# uNimbus_board_2_v1_2.net
KiCad netlist of a schematic drawn in EAGLE
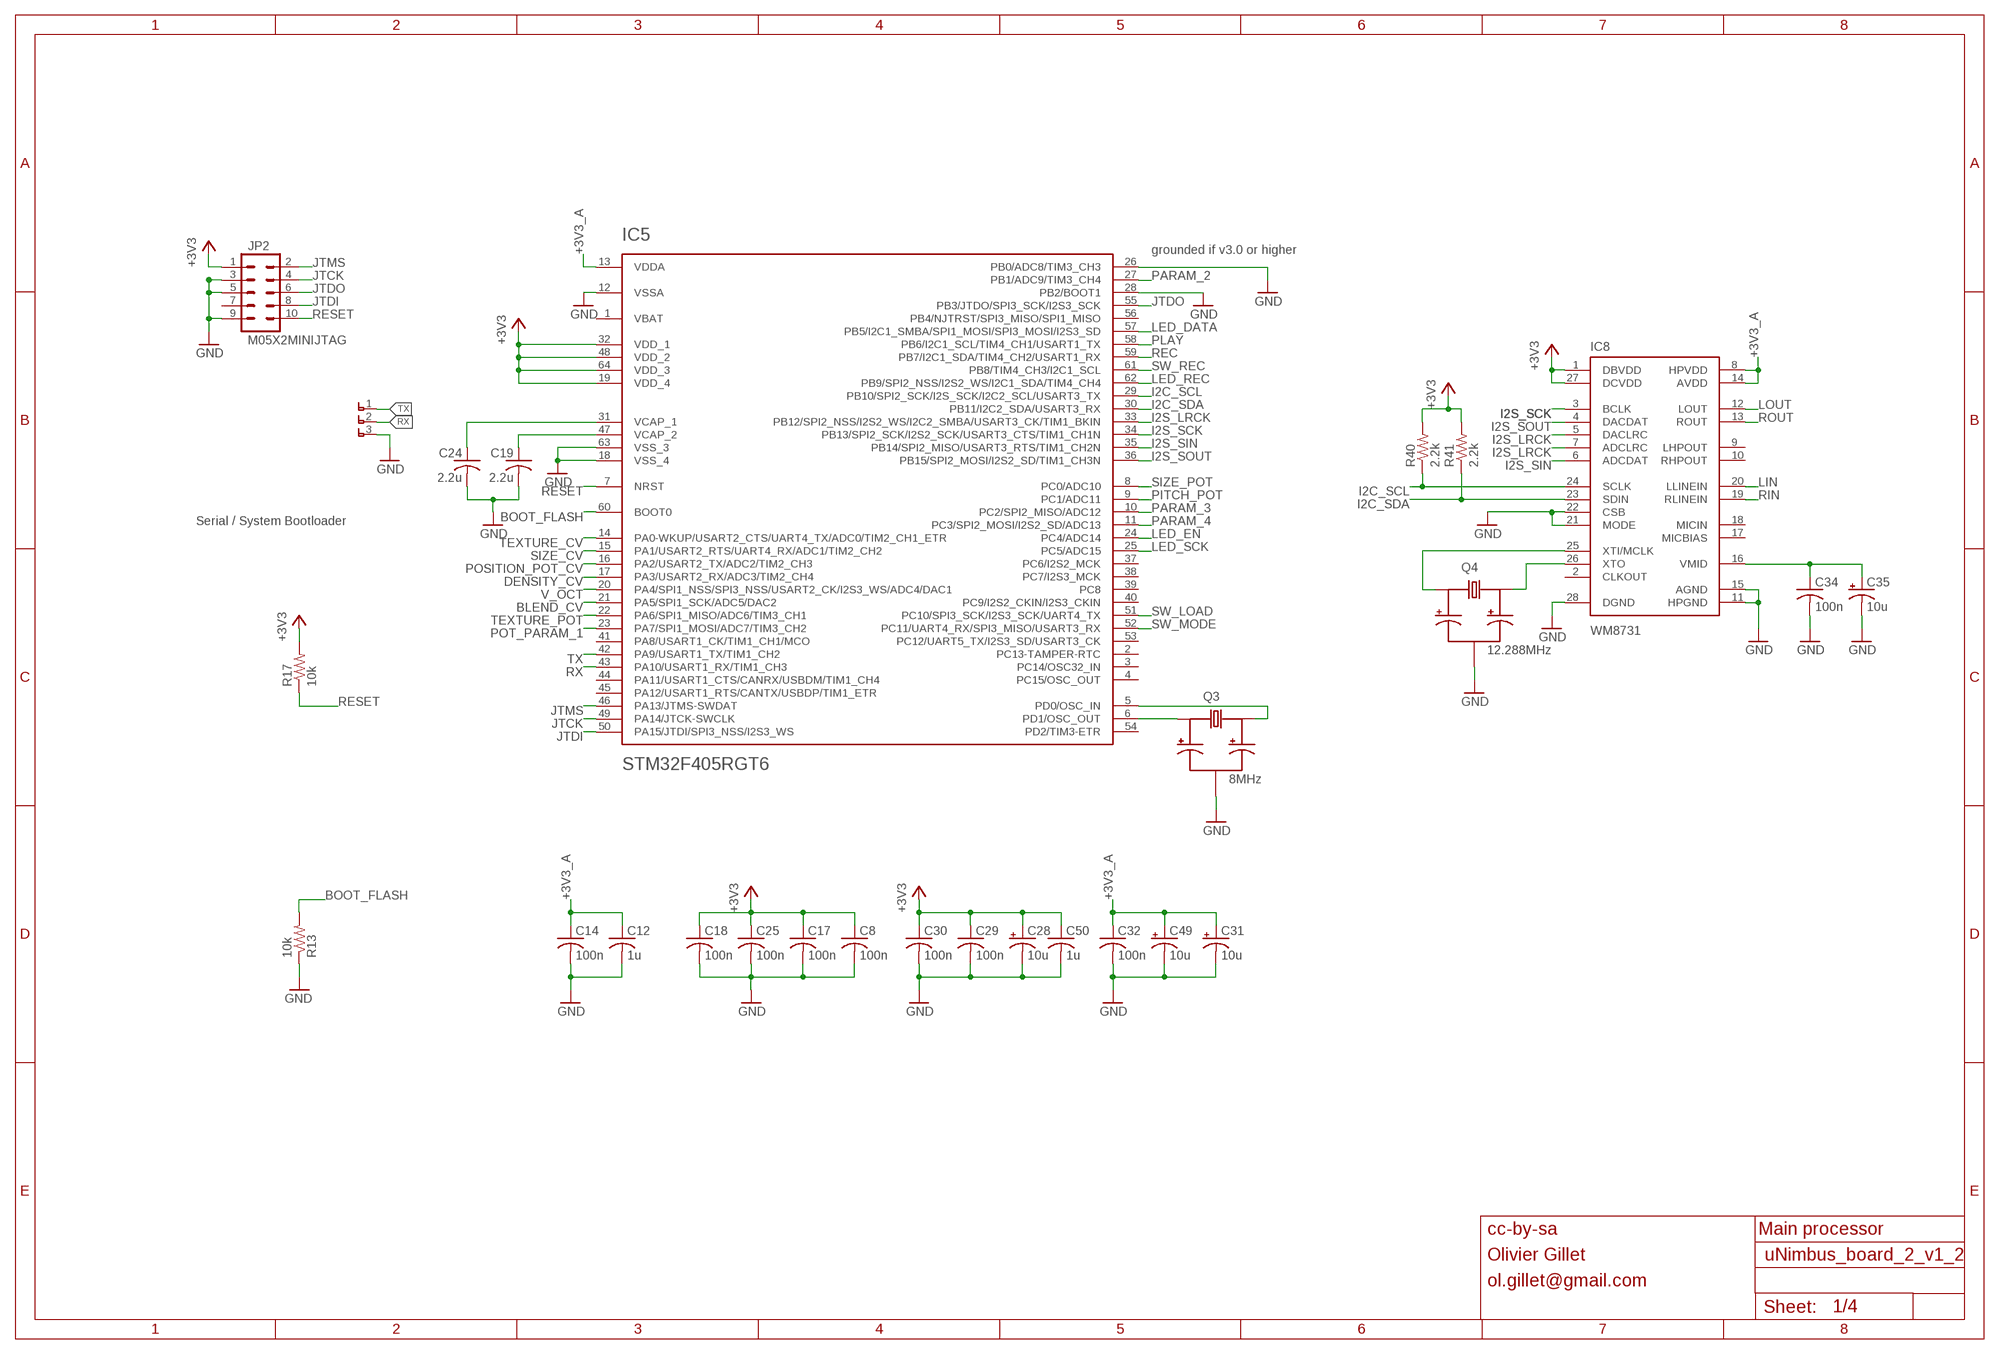
[diagram p0: schematic, sheet 1]
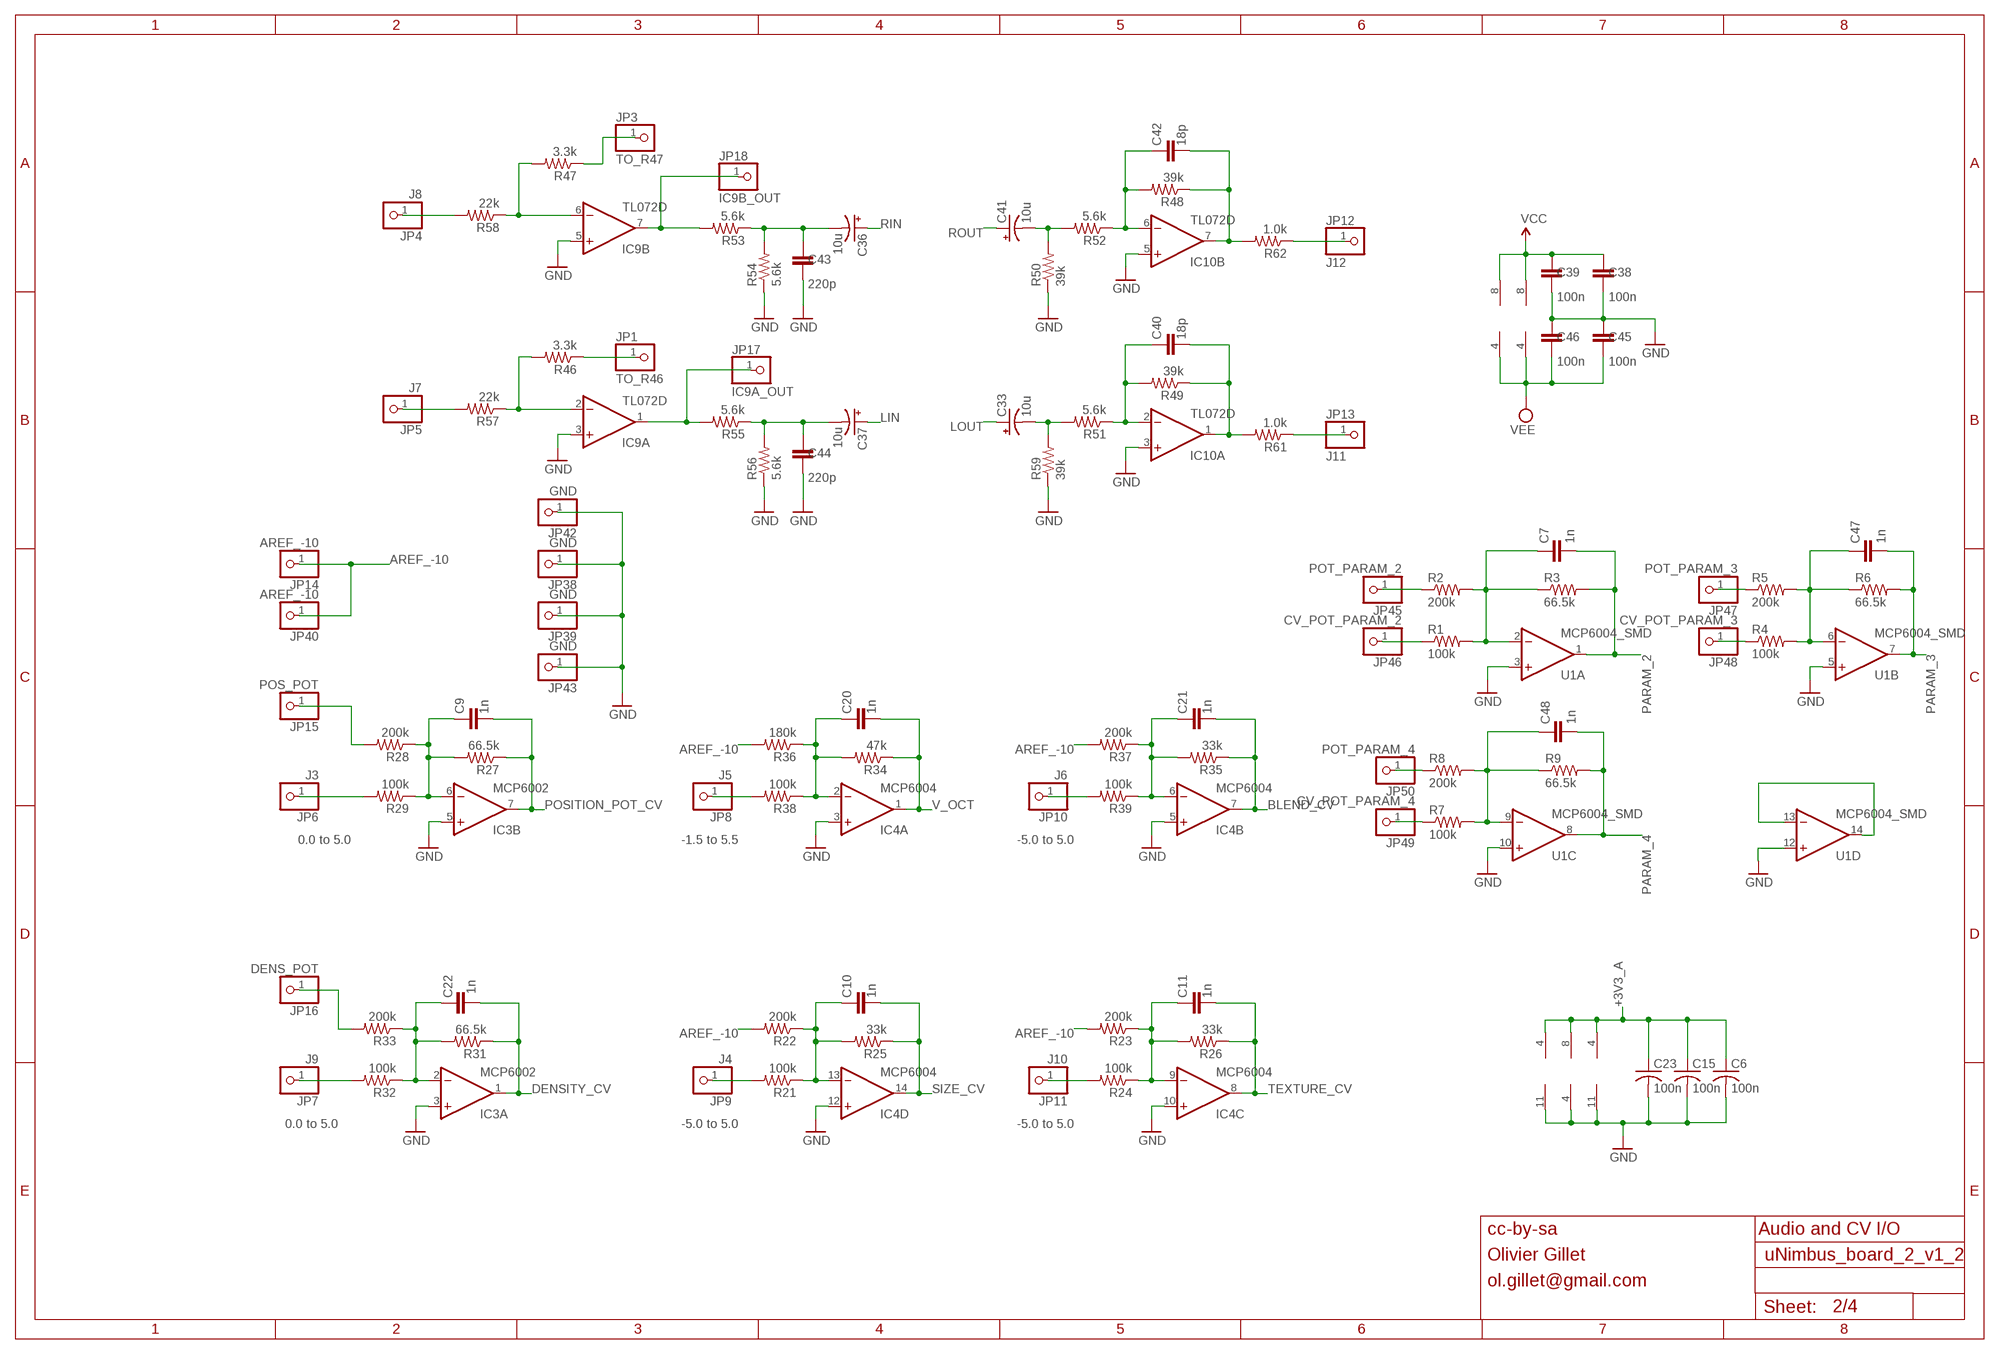
[diagram p1: schematic, sheet 2]
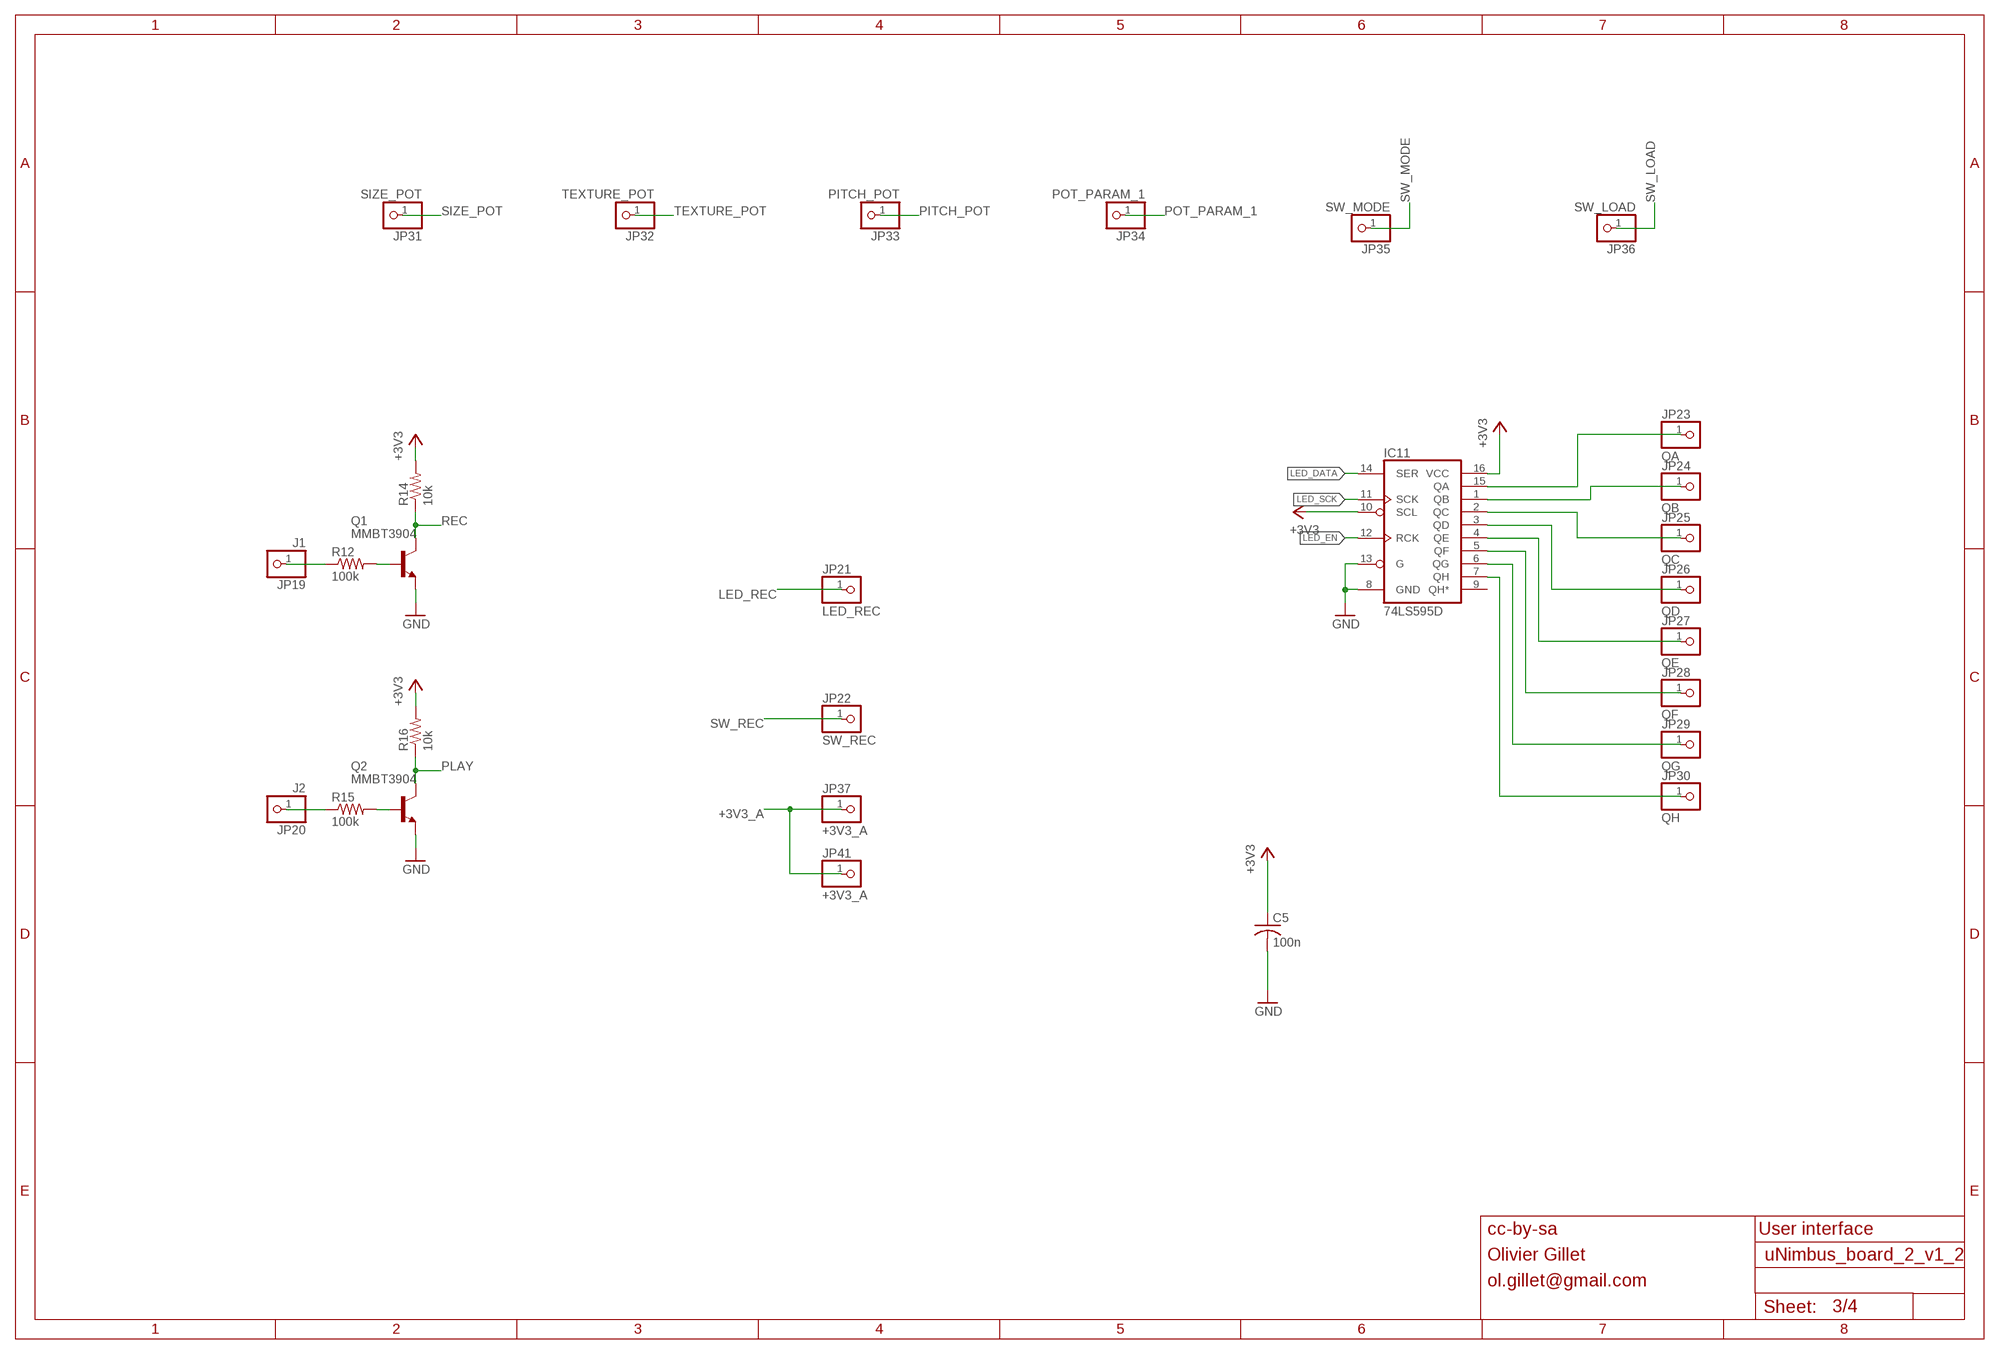
[diagram p2: schematic, sheet 3]
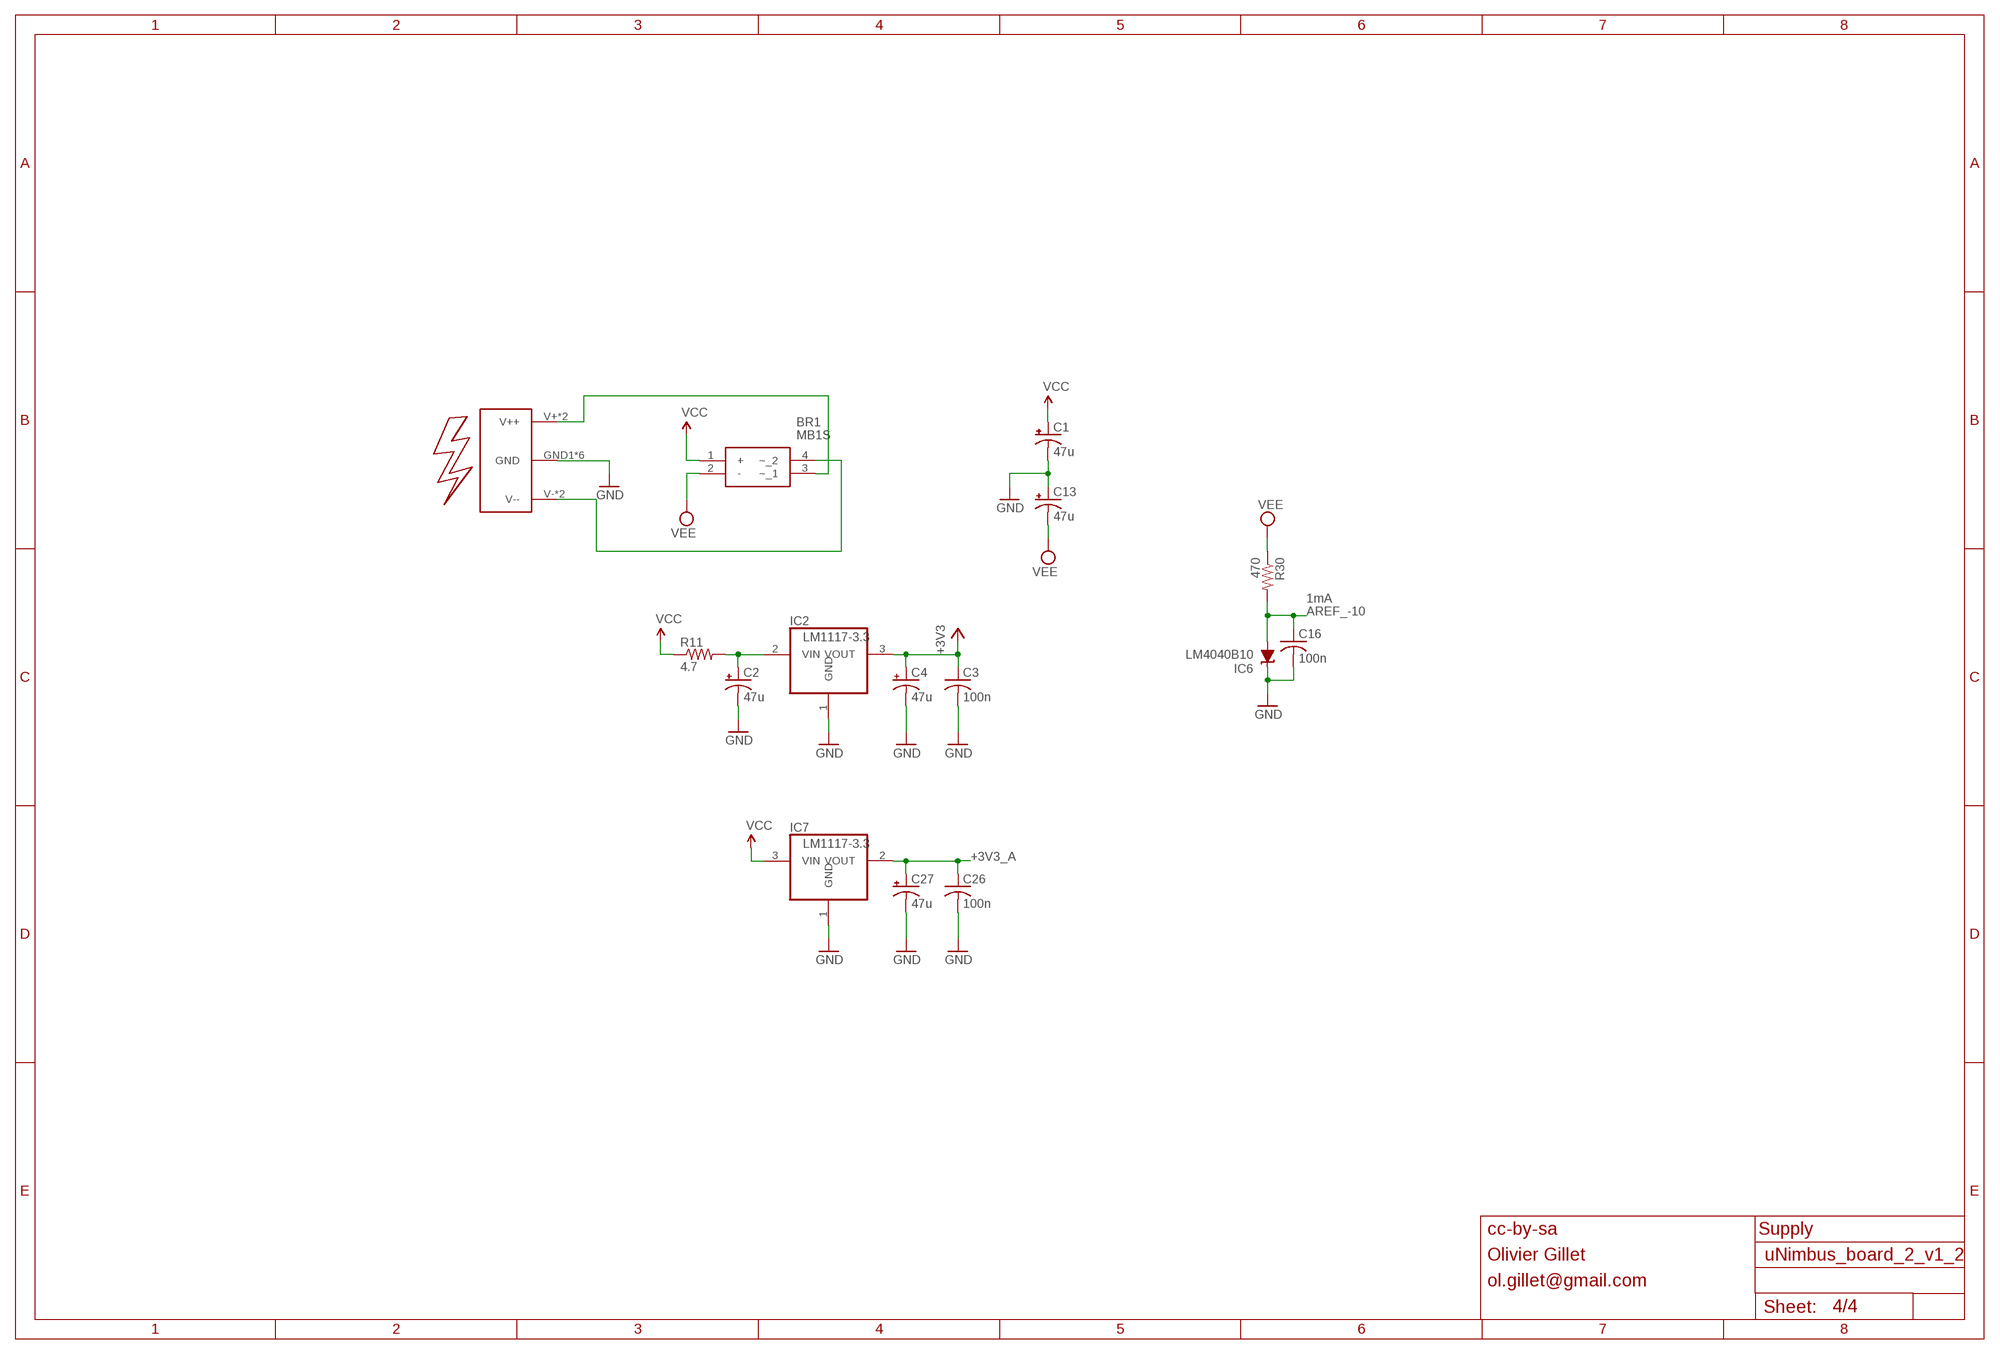
[diagram p3: schematic, sheet 4]

(export (version "E")
  (design (tool "Eeschema 10.0.6"))
  (components
    (comp (ref "C6")
      (value "100n")
      (footprint "eagle-import:C0603K")
      (libsource (lib "eagle-import") (part "rcl@1_C-USC0603K"))
    )
    (comp (ref "C7")
      (value "1n")
      (footprint "eagle-import:PARTS_AMAN_RESISTOR_0603")
      (libsource (lib "eagle-import") (part "PARTS_AMAN_CAPACITOR"))
    )
    (comp (ref "C9")
      (value "1n")
      (footprint "eagle-import:PARTS_AMAN_RESISTOR_0603")
      (libsource (lib "eagle-import") (part "PARTS_AMAN_CAPACITOR"))
    )
    (comp (ref "C10")
      (value "1n")
      (footprint "eagle-import:PARTS_AMAN_RESISTOR_0603")
      (libsource (lib "eagle-import") (part "PARTS_AMAN_CAPACITOR"))
    )
    (comp (ref "C11")
      (value "1n")
      (footprint "eagle-import:PARTS_AMAN_RESISTOR_0603")
      (libsource (lib "eagle-import") (part "PARTS_AMAN_CAPACITOR"))
    )
    (comp (ref "C15")
      (value "100n")
      (footprint "eagle-import:C0603K")
      (libsource (lib "eagle-import") (part "rcl@1_C-USC0603K"))
    )
    (comp (ref "C20")
      (value "1n")
      (footprint "eagle-import:PARTS_AMAN_RESISTOR_0603")
      (libsource (lib "eagle-import") (part "PARTS_AMAN_CAPACITOR"))
    )
    (comp (ref "C21")
      (value "1n")
      (footprint "eagle-import:PARTS_AMAN_RESISTOR_0603")
      (libsource (lib "eagle-import") (part "PARTS_AMAN_CAPACITOR"))
    )
    (comp (ref "C22")
      (value "1n")
      (footprint "eagle-import:PARTS_AMAN_RESISTOR_0603")
      (libsource (lib "eagle-import") (part "PARTS_AMAN_CAPACITOR"))
    )
    (comp (ref "C23")
      (value "100n")
      (footprint "eagle-import:C0603")
      (libsource (lib "eagle-import") (part "C-USC0603"))
    )
    (comp (ref "C33")
      (value "10u")
      (footprint "eagle-import:PANASONIC_B")
      (libsource (lib "eagle-import") (part "CPOL-USB"))
    )
    (comp (ref "C36")
      (value "10u")
      (footprint "eagle-import:PANASONIC_B")
      (libsource (lib "eagle-import") (part "CPOL-USB"))
    )
    (comp (ref "C37")
      (value "10u")
      (footprint "eagle-import:PANASONIC_B")
      (libsource (lib "eagle-import") (part "CPOL-USB"))
    )
    (comp (ref "C38")
      (value "100n")
      (footprint "eagle-import:PARTS_AMAN_RESISTOR_0603")
      (libsource (lib "eagle-import") (part "PARTS_AMAN_CAPACITOR"))
    )
    (comp (ref "C39")
      (value "100n")
      (footprint "eagle-import:PARTS_AMAN_RESISTOR_0603")
      (libsource (lib "eagle-import") (part "PARTS_AMAN_CAPACITOR"))
    )
    (comp (ref "C40")
      (value "18p")
      (footprint "eagle-import:PARTS_AMAN_RESISTOR_0603")
      (libsource (lib "eagle-import") (part "PARTS_AMAN_CAPACITOR"))
    )
    (comp (ref "C41")
      (value "10u")
      (footprint "eagle-import:PANASONIC_B")
      (libsource (lib "eagle-import") (part "CPOL-USB"))
    )
    (comp (ref "C42")
      (value "18p")
      (footprint "eagle-import:PARTS_AMAN_RESISTOR_0603")
      (libsource (lib "eagle-import") (part "PARTS_AMAN_CAPACITOR"))
    )
    (comp (ref "C43")
      (value "220p")
      (footprint "eagle-import:PARTS_AMAN_RESISTOR_0603")
      (libsource (lib "eagle-import") (part "PARTS_AMAN_CAPACITOR"))
    )
    (comp (ref "C44")
      (value "220p")
      (footprint "eagle-import:PARTS_AMAN_RESISTOR_0603")
      (libsource (lib "eagle-import") (part "PARTS_AMAN_CAPACITOR"))
    )
    (comp (ref "C45")
      (value "100n")
      (footprint "eagle-import:PARTS_AMAN_RESISTOR_0603")
      (libsource (lib "eagle-import") (part "PARTS_AMAN_CAPACITOR"))
    )
    (comp (ref "C46")
      (value "100n")
      (footprint "eagle-import:PARTS_AMAN_RESISTOR_0603")
      (libsource (lib "eagle-import") (part "PARTS_AMAN_CAPACITOR"))
    )
    (comp (ref "C47")
      (value "1n")
      (footprint "eagle-import:PARTS_AMAN_RESISTOR_0603")
      (libsource (lib "eagle-import") (part "PARTS_AMAN_CAPACITOR"))
    )
    (comp (ref "C48")
      (value "1n")
      (footprint "eagle-import:PARTS_AMAN_RESISTOR_0603")
      (libsource (lib "eagle-import") (part "PARTS_AMAN_CAPACITOR"))
    )
    (comp (ref "IC3")
      (value "MCP6002")
      (footprint "eagle-import:SO08")
      (libsource (lib "eagle-import") (part "TL072D"))
    )
    (comp (ref "IC4")
      (value "MCP6004")
      (footprint "eagle-import:SO14")
      (libsource (lib "eagle-import") (part "TL074D"))
    )
    (comp (ref "IC9")
      (value "TL072D")
      (footprint "eagle-import:SO08")
      (libsource (lib "eagle-import") (part "og-linear_TL072D"))
    )
    (comp (ref "IC10")
      (value "TL072D")
      (footprint "eagle-import:SO08")
      (libsource (lib "eagle-import") (part "og-linear_TL072D"))
    )
    (comp (ref "JP1")
      (value "TO_R46")
      (footprint "eagle-import:PARTS_AMAN_1X01")
      (libsource (lib "eagle-import") (part "PARTS_AMAN_PINHD-1X1"))
    )
    (comp (ref "JP3")
      (value "TO_R47")
      (footprint "eagle-import:PARTS_AMAN_1X01")
      (libsource (lib "eagle-import") (part "PARTS_AMAN_PINHD-1X1"))
    )
    (comp (ref "JP4")
      (value "J8")
      (footprint "eagle-import:PARTS_AMAN_1X01")
      (libsource (lib "eagle-import") (part "PARTS_AMAN_PINHD-1X1"))
    )
    (comp (ref "JP5")
      (value "J7")
      (footprint "eagle-import:PARTS_AMAN_1X01")
      (libsource (lib "eagle-import") (part "PARTS_AMAN_PINHD-1X1"))
    )
    (comp (ref "JP6")
      (value "J3")
      (footprint "eagle-import:PARTS_AMAN_1X01")
      (libsource (lib "eagle-import") (part "PARTS_AMAN_PINHD-1X1"))
    )
    (comp (ref "JP7")
      (value "J9")
      (footprint "eagle-import:PARTS_AMAN_1X01")
      (libsource (lib "eagle-import") (part "PARTS_AMAN_PINHD-1X1"))
    )
    (comp (ref "JP8")
      (value "J5")
      (footprint "eagle-import:PARTS_AMAN_1X01")
      (libsource (lib "eagle-import") (part "PARTS_AMAN_PINHD-1X1"))
    )
    (comp (ref "JP9")
      (value "J4")
      (footprint "eagle-import:PARTS_AMAN_1X01")
      (libsource (lib "eagle-import") (part "PARTS_AMAN_PINHD-1X1"))
    )
    (comp (ref "JP10")
      (value "J6")
      (footprint "eagle-import:PARTS_AMAN_1X01")
      (libsource (lib "eagle-import") (part "PARTS_AMAN_PINHD-1X1"))
    )
    (comp (ref "JP11")
      (value "J10")
      (footprint "eagle-import:PARTS_AMAN_1X01")
      (libsource (lib "eagle-import") (part "PARTS_AMAN_PINHD-1X1"))
    )
    (comp (ref "JP12")
      (value "J12")
      (footprint "eagle-import:PARTS_AMAN_1X01")
      (libsource (lib "eagle-import") (part "PARTS_AMAN_PINHD-1X1"))
    )
    (comp (ref "JP13")
      (value "J11")
      (footprint "eagle-import:PARTS_AMAN_1X01")
      (libsource (lib "eagle-import") (part "PARTS_AMAN_PINHD-1X1"))
    )
    (comp (ref "JP14")
      (value "AREF_-10")
      (footprint "eagle-import:PARTS_AMAN_1X01")
      (libsource (lib "eagle-import") (part "PARTS_AMAN_PINHD-1X1"))
    )
    (comp (ref "JP15")
      (value "POS_POT")
      (footprint "eagle-import:PARTS_AMAN_1X01")
      (libsource (lib "eagle-import") (part "PARTS_AMAN_PINHD-1X1"))
    )
    (comp (ref "JP16")
      (value "DENS_POT")
      (footprint "eagle-import:PARTS_AMAN_1X01")
      (libsource (lib "eagle-import") (part "PARTS_AMAN_PINHD-1X1"))
    )
    (comp (ref "JP17")
      (value "IC9A_OUT")
      (footprint "eagle-import:PARTS_AMAN_1X01")
      (libsource (lib "eagle-import") (part "PARTS_AMAN_PINHD-1X1"))
    )
    (comp (ref "JP18")
      (value "IC9B_OUT")
      (footprint "eagle-import:PARTS_AMAN_1X01")
      (libsource (lib "eagle-import") (part "PARTS_AMAN_PINHD-1X1"))
    )
    (comp (ref "JP38")
      (value "GND")
      (footprint "eagle-import:PARTS_AMAN_1X01")
      (libsource (lib "eagle-import") (part "PARTS_AMAN_PINHD-1X1"))
    )
    (comp (ref "JP39")
      (value "GND")
      (footprint "eagle-import:PARTS_AMAN_1X01")
      (libsource (lib "eagle-import") (part "PARTS_AMAN_PINHD-1X1"))
    )
    (comp (ref "JP40")
      (value "AREF_-10")
      (footprint "eagle-import:PARTS_AMAN_1X01")
      (libsource (lib "eagle-import") (part "PARTS_AMAN_PINHD-1X1"))
    )
    (comp (ref "JP42")
      (value "GND")
      (footprint "eagle-import:PARTS_AMAN_1X01")
      (libsource (lib "eagle-import") (part "PARTS_AMAN_PINHD-1X1"))
    )
    (comp (ref "JP43")
      (value "GND")
      (footprint "eagle-import:PARTS_AMAN_1X01")
      (libsource (lib "eagle-import") (part "PARTS_AMAN_PINHD-1X1"))
    )
    (comp (ref "JP45")
      (value "POT_PARAM_2")
      (footprint "eagle-import:PARTS_AMAN_1X01")
      (libsource (lib "eagle-import") (part "PARTS_AMAN_PINHD-1X1"))
    )
    (comp (ref "JP46")
      (value "CV_POT_PARAM_2")
      (footprint "eagle-import:PARTS_AMAN_1X01")
      (libsource (lib "eagle-import") (part "PARTS_AMAN_PINHD-1X1"))
    )
    (comp (ref "JP47")
      (value "POT_PARAM_3")
      (footprint "eagle-import:PARTS_AMAN_1X01")
      (libsource (lib "eagle-import") (part "PARTS_AMAN_PINHD-1X1"))
    )
    (comp (ref "JP48")
      (value "CV_POT_PARAM_3")
      (footprint "eagle-import:PARTS_AMAN_1X01")
      (libsource (lib "eagle-import") (part "PARTS_AMAN_PINHD-1X1"))
    )
    (comp (ref "JP49")
      (value "CV_POT_PARAM_4")
      (footprint "eagle-import:PARTS_AMAN_1X01")
      (libsource (lib "eagle-import") (part "PARTS_AMAN_PINHD-1X1"))
    )
    (comp (ref "JP50")
      (value "POT_PARAM_4")
      (footprint "eagle-import:PARTS_AMAN_1X01")
      (libsource (lib "eagle-import") (part "PARTS_AMAN_PINHD-1X1"))
    )
    (comp (ref "R1")
      (value "100k")
      (footprint "eagle-import:PARTS_AMAN_RESISTOR_0603")
      (libsource (lib "eagle-import") (part "PARTS_AMAN_RESISTOR"))
    )
    (comp (ref "R2")
      (value "200k")
      (footprint "eagle-import:PARTS_AMAN_RESISTOR_0603")
      (libsource (lib "eagle-import") (part "PARTS_AMAN_RESISTOR"))
    )
    (comp (ref "R3")
      (value "66.5k")
      (footprint "eagle-import:PARTS_AMAN_RESISTOR_0603")
      (libsource (lib "eagle-import") (part "PARTS_AMAN_RESISTOR"))
    )
    (comp (ref "R4")
      (value "100k")
      (footprint "eagle-import:PARTS_AMAN_RESISTOR_0603")
      (libsource (lib "eagle-import") (part "PARTS_AMAN_RESISTOR"))
    )
    (comp (ref "R5")
      (value "200k")
      (footprint "eagle-import:PARTS_AMAN_RESISTOR_0603")
      (libsource (lib "eagle-import") (part "PARTS_AMAN_RESISTOR"))
    )
    (comp (ref "R6")
      (value "66.5k")
      (footprint "eagle-import:PARTS_AMAN_RESISTOR_0603")
      (libsource (lib "eagle-import") (part "PARTS_AMAN_RESISTOR"))
    )
    (comp (ref "R7")
      (value "100k")
      (footprint "eagle-import:PARTS_AMAN_RESISTOR_0603")
      (libsource (lib "eagle-import") (part "PARTS_AMAN_RESISTOR"))
    )
    (comp (ref "R8")
      (value "200k")
      (footprint "eagle-import:PARTS_AMAN_RESISTOR_0603")
      (libsource (lib "eagle-import") (part "PARTS_AMAN_RESISTOR"))
    )
    (comp (ref "R9")
      (value "66.5k")
      (footprint "eagle-import:PARTS_AMAN_RESISTOR_0603")
      (libsource (lib "eagle-import") (part "PARTS_AMAN_RESISTOR"))
    )
    (comp (ref "R21")
      (value "100k")
      (footprint "eagle-import:PARTS_AMAN_RESISTOR_0603")
      (libsource (lib "eagle-import") (part "PARTS_AMAN_RESISTOR"))
    )
    (comp (ref "R22")
      (value "200k")
      (footprint "eagle-import:PARTS_AMAN_RESISTOR_0603")
      (libsource (lib "eagle-import") (part "PARTS_AMAN_RESISTOR"))
    )
    (comp (ref "R23")
      (value "200k")
      (footprint "eagle-import:PARTS_AMAN_RESISTOR_0603")
      (libsource (lib "eagle-import") (part "PARTS_AMAN_RESISTOR"))
    )
    (comp (ref "R24")
      (value "100k")
      (footprint "eagle-import:PARTS_AMAN_RESISTOR_0603")
      (libsource (lib "eagle-import") (part "PARTS_AMAN_RESISTOR"))
    )
    (comp (ref "R25")
      (value "33k")
      (footprint "eagle-import:PARTS_AMAN_RESISTOR_0603")
      (libsource (lib "eagle-import") (part "PARTS_AMAN_RESISTOR"))
    )
    (comp (ref "R26")
      (value "33k")
      (footprint "eagle-import:PARTS_AMAN_RESISTOR_0603")
      (libsource (lib "eagle-import") (part "PARTS_AMAN_RESISTOR"))
    )
    (comp (ref "R27")
      (value "66.5k")
      (footprint "eagle-import:PARTS_AMAN_RESISTOR_0603")
      (libsource (lib "eagle-import") (part "PARTS_AMAN_RESISTOR"))
    )
    (comp (ref "R28")
      (value "200k")
      (footprint "eagle-import:PARTS_AMAN_RESISTOR_0603")
      (libsource (lib "eagle-import") (part "PARTS_AMAN_RESISTOR"))
    )
    (comp (ref "R29")
      (value "100k")
      (footprint "eagle-import:PARTS_AMAN_RESISTOR_0603")
      (libsource (lib "eagle-import") (part "PARTS_AMAN_RESISTOR"))
    )
    (comp (ref "R31")
      (value "66.5k")
      (footprint "eagle-import:PARTS_AMAN_RESISTOR_0603")
      (libsource (lib "eagle-import") (part "PARTS_AMAN_RESISTOR"))
    )
    (comp (ref "R32")
      (value "100k")
      (footprint "eagle-import:PARTS_AMAN_RESISTOR_0603")
      (libsource (lib "eagle-import") (part "PARTS_AMAN_RESISTOR"))
    )
    (comp (ref "R33")
      (value "200k")
      (footprint "eagle-import:PARTS_AMAN_RESISTOR_0603")
      (libsource (lib "eagle-import") (part "PARTS_AMAN_RESISTOR"))
    )
    (comp (ref "R34")
      (value "47k")
      (footprint "eagle-import:PARTS_AMAN_RESISTOR_0603")
      (libsource (lib "eagle-import") (part "PARTS_AMAN_RESISTOR"))
    )
    (comp (ref "R35")
      (value "33k")
      (footprint "eagle-import:PARTS_AMAN_RESISTOR_0603")
      (libsource (lib "eagle-import") (part "PARTS_AMAN_RESISTOR"))
    )
    (comp (ref "R36")
      (value "180k")
      (footprint "eagle-import:PARTS_AMAN_RESISTOR_0603")
      (libsource (lib "eagle-import") (part "PARTS_AMAN_RESISTOR"))
    )
    (comp (ref "R37")
      (value "200k")
      (footprint "eagle-import:PARTS_AMAN_RESISTOR_0603")
      (libsource (lib "eagle-import") (part "PARTS_AMAN_RESISTOR"))
    )
    (comp (ref "R38")
      (value "100k")
      (footprint "eagle-import:PARTS_AMAN_RESISTOR_0603")
      (libsource (lib "eagle-import") (part "PARTS_AMAN_RESISTOR"))
    )
    (comp (ref "R39")
      (value "100k")
      (footprint "eagle-import:PARTS_AMAN_RESISTOR_0603")
      (libsource (lib "eagle-import") (part "PARTS_AMAN_RESISTOR"))
    )
    (comp (ref "R46")
      (value "3.3k")
      (footprint "eagle-import:PARTS_AMAN_RESISTOR_0603")
      (libsource (lib "eagle-import") (part "PARTS_AMAN_RESISTOR"))
    )
    (comp (ref "R47")
      (value "3.3k")
      (footprint "eagle-import:PARTS_AMAN_RESISTOR_0603")
      (libsource (lib "eagle-import") (part "PARTS_AMAN_RESISTOR"))
    )
    (comp (ref "R48")
      (value "39k")
      (footprint "eagle-import:PARTS_AMAN_RESISTOR_0603")
      (libsource (lib "eagle-import") (part "PARTS_AMAN_RESISTOR"))
    )
    (comp (ref "R49")
      (value "39k")
      (footprint "eagle-import:PARTS_AMAN_RESISTOR_0603")
      (libsource (lib "eagle-import") (part "PARTS_AMAN_RESISTOR"))
    )
    (comp (ref "R50")
      (value "39k")
      (footprint "eagle-import:PARTS_AMAN_RESISTOR_0603")
      (libsource (lib "eagle-import") (part "PARTS_AMAN_RESISTOR"))
    )
    (comp (ref "R51")
      (value "5.6k")
      (footprint "eagle-import:PARTS_AMAN_RESISTOR_0603")
      (libsource (lib "eagle-import") (part "PARTS_AMAN_RESISTOR"))
    )
    (comp (ref "R52")
      (value "5.6k")
      (footprint "eagle-import:PARTS_AMAN_RESISTOR_0603")
      (libsource (lib "eagle-import") (part "PARTS_AMAN_RESISTOR"))
    )
    (comp (ref "R53")
      (value "5.6k")
      (footprint "eagle-import:PARTS_AMAN_RESISTOR_0603")
      (libsource (lib "eagle-import") (part "PARTS_AMAN_RESISTOR"))
    )
    (comp (ref "R54")
      (value "5.6k")
      (footprint "eagle-import:PARTS_AMAN_RESISTOR_0603")
      (libsource (lib "eagle-import") (part "PARTS_AMAN_RESISTOR"))
    )
    (comp (ref "R55")
      (value "5.6k")
      (footprint "eagle-import:PARTS_AMAN_RESISTOR_0603")
      (libsource (lib "eagle-import") (part "PARTS_AMAN_RESISTOR"))
    )
    (comp (ref "R56")
      (value "5.6k")
      (footprint "eagle-import:PARTS_AMAN_RESISTOR_0603")
      (libsource (lib "eagle-import") (part "PARTS_AMAN_RESISTOR"))
    )
    (comp (ref "R57")
      (value "22k")
      (footprint "eagle-import:PARTS_AMAN_RESISTOR_0603")
      (libsource (lib "eagle-import") (part "PARTS_AMAN_RESISTOR"))
    )
    (comp (ref "R58")
      (value "22k")
      (footprint "eagle-import:PARTS_AMAN_RESISTOR_0603")
      (libsource (lib "eagle-import") (part "PARTS_AMAN_RESISTOR"))
    )
    (comp (ref "R59")
      (value "39k")
      (footprint "eagle-import:PARTS_AMAN_RESISTOR_0603")
      (libsource (lib "eagle-import") (part "PARTS_AMAN_RESISTOR"))
    )
    (comp (ref "R61")
      (value "1.0k")
      (footprint "eagle-import:PARTS_AMAN_RESISTOR_0603")
      (libsource (lib "eagle-import") (part "PARTS_AMAN_RESISTOR"))
    )
    (comp (ref "R62")
      (value "1.0k")
      (footprint "eagle-import:PARTS_AMAN_RESISTOR_0603")
      (libsource (lib "eagle-import") (part "PARTS_AMAN_RESISTOR"))
    )
    (comp (ref "U1")
      (value "MCP6004_SMD")
      (footprint "eagle-import:SO14")
      (libsource (lib "eagle-import") (part "MCP6004_SMD"))
    )
    (comp (ref "C5")
      (value "100n")
      (footprint "eagle-import:C0603")
      (libsource (lib "eagle-import") (part "C-USC0603"))
    )
    (comp (ref "IC11")
      (value "74LS595D")
      (footprint "eagle-import:SO16")
      (libsource (lib "eagle-import") (part "74595DLS"))
    )
    (comp (ref "JP19")
      (value "J1")
      (footprint "eagle-import:PARTS_AMAN_1X01")
      (libsource (lib "eagle-import") (part "PARTS_AMAN_PINHD-1X1"))
    )
    (comp (ref "JP20")
      (value "J2")
      (footprint "eagle-import:PARTS_AMAN_1X01")
      (libsource (lib "eagle-import") (part "PARTS_AMAN_PINHD-1X1"))
    )
    (comp (ref "JP21")
      (value "LED_REC")
      (footprint "eagle-import:PARTS_AMAN_1X01")
      (libsource (lib "eagle-import") (part "PARTS_AMAN_PINHD-1X1"))
    )
    (comp (ref "JP22")
      (value "SW_REC")
      (footprint "eagle-import:PARTS_AMAN_1X01")
      (libsource (lib "eagle-import") (part "PARTS_AMAN_PINHD-1X1"))
    )
    (comp (ref "JP23")
      (value "QA")
      (footprint "eagle-import:PARTS_AMAN_1X01")
      (libsource (lib "eagle-import") (part "PARTS_AMAN_PINHD-1X1"))
    )
    (comp (ref "JP24")
      (value "QB")
      (footprint "eagle-import:PARTS_AMAN_1X01")
      (libsource (lib "eagle-import") (part "PARTS_AMAN_PINHD-1X1"))
    )
    (comp (ref "JP25")
      (value "QC")
      (footprint "eagle-import:PARTS_AMAN_1X01")
      (libsource (lib "eagle-import") (part "PARTS_AMAN_PINHD-1X1"))
    )
    (comp (ref "JP26")
      (value "QD")
      (footprint "eagle-import:PARTS_AMAN_1X01")
      (libsource (lib "eagle-import") (part "PARTS_AMAN_PINHD-1X1"))
    )
    (comp (ref "JP27")
      (value "QE")
      (footprint "eagle-import:PARTS_AMAN_1X01")
      (libsource (lib "eagle-import") (part "PARTS_AMAN_PINHD-1X1"))
    )
    (comp (ref "JP28")
      (value "QF")
      (footprint "eagle-import:PARTS_AMAN_1X01")
      (libsource (lib "eagle-import") (part "PARTS_AMAN_PINHD-1X1"))
    )
    (comp (ref "JP29")
      (value "QG")
      (footprint "eagle-import:PARTS_AMAN_1X01")
      (libsource (lib "eagle-import") (part "PARTS_AMAN_PINHD-1X1"))
    )
    (comp (ref "JP30")
      (value "QH")
      (footprint "eagle-import:PARTS_AMAN_1X01")
      (libsource (lib "eagle-import") (part "PARTS_AMAN_PINHD-1X1"))
    )
    (comp (ref "JP31")
      (value "SIZE_POT")
      (footprint "eagle-import:PARTS_AMAN_1X01")
      (libsource (lib "eagle-import") (part "PARTS_AMAN_PINHD-1X1"))
    )
    (comp (ref "JP32")
      (value "TEXTURE_POT")
      (footprint "eagle-import:PARTS_AMAN_1X01")
      (libsource (lib "eagle-import") (part "PARTS_AMAN_PINHD-1X1"))
    )
    (comp (ref "JP33")
      (value "PITCH_POT")
      (footprint "eagle-import:PARTS_AMAN_1X01")
      (libsource (lib "eagle-import") (part "PARTS_AMAN_PINHD-1X1"))
    )
    (comp (ref "JP34")
      (value "POT_PARAM_1")
      (footprint "eagle-import:PARTS_AMAN_1X01")
      (libsource (lib "eagle-import") (part "PARTS_AMAN_PINHD-1X1"))
    )
    (comp (ref "JP35")
      (value "SW_MODE")
      (footprint "eagle-import:PARTS_AMAN_1X01")
      (libsource (lib "eagle-import") (part "PARTS_AMAN_PINHD-1X1"))
    )
    (comp (ref "JP36")
      (value "SW_LOAD")
      (footprint "eagle-import:PARTS_AMAN_1X01")
      (libsource (lib "eagle-import") (part "PARTS_AMAN_PINHD-1X1"))
    )
    (comp (ref "JP37")
      (value "+3V3_A")
      (footprint "eagle-import:PARTS_AMAN_1X01")
      (libsource (lib "eagle-import") (part "PARTS_AMAN_PINHD-1X1"))
    )
    (comp (ref "JP41")
      (value "+3V3_A")
      (footprint "eagle-import:PARTS_AMAN_1X01")
      (libsource (lib "eagle-import") (part "PARTS_AMAN_PINHD-1X1"))
    )
    (comp (ref "Q1")
      (value "MMBT3904")
      (footprint "eagle-import:SOT23-BEC")
      (libsource (lib "eagle-import") (part "-NPN-SOT23-BECMMBT3904LT1"))
    )
    (comp (ref "Q2")
      (value "MMBT3904")
      (footprint "eagle-import:SOT23-BEC")
      (libsource (lib "eagle-import") (part "-NPN-SOT23-BECMMBT3904LT1"))
    )
    (comp (ref "R12")
      (value "100k")
      (footprint "eagle-import:R0603")
      (libsource (lib "eagle-import") (part "R-US_R0603"))
    )
    (comp (ref "R14")
      (value "10k")
      (footprint "eagle-import:R0603")
      (libsource (lib "eagle-import") (part "R-US_R0603"))
    )
    (comp (ref "R15")
      (value "100k")
      (footprint "eagle-import:R0603")
      (libsource (lib "eagle-import") (part "R-US_R0603"))
    )
    (comp (ref "R16")
      (value "10k")
      (footprint "eagle-import:R0603")
      (libsource (lib "eagle-import") (part "R-US_R0603"))
    )
    (comp (ref "BR1")
      (value "MB1S")
      (footprint "eagle-import:SOP245P670X290-4N")
      (fields (field (name "MOUSER_PART_NUMBER") "512-MB1S") (field (name "RS_PART_NUMBER") "7613650P"))
      (libsource (lib "eagle-import") (part "MB1S"))
    )
    (comp (ref "C1")
      (value "47u")
      (footprint "eagle-import:153CLV-0505")
      (libsource (lib "eagle-import") (part "CPOL-US153CLV-0505"))
    )
    (comp (ref "C2")
      (value "47u")
      (footprint "eagle-import:153CLV-0505")
      (libsource (lib "eagle-import") (part "rcl@1_CPOL-US153CLV-0505"))
    )
    (comp (ref "C3")
      (value "100n")
      (footprint "eagle-import:C0603")
      (libsource (lib "eagle-import") (part "C-USC0603"))
    )
    (comp (ref "C4")
      (value "47u")
      (footprint "eagle-import:153CLV-0505")
      (libsource (lib "eagle-import") (part "CPOL-US153CLV-0505"))
    )
    (comp (ref "C13")
      (value "47u")
      (footprint "eagle-import:153CLV-0505")
      (libsource (lib "eagle-import") (part "CPOL-US153CLV-0505"))
    )
    (comp (ref "C16")
      (value "100n")
      (footprint "eagle-import:C0603")
      (libsource (lib "eagle-import") (part "C-USC0603"))
    )
    (comp (ref "C26")
      (value "100n")
      (footprint "eagle-import:C0603")
      (libsource (lib "eagle-import") (part "C-USC0603"))
    )
    (comp (ref "C27")
      (value "47u")
      (footprint "eagle-import:153CLV-0505")
      (libsource (lib "eagle-import") (part "CPOL-US153CLV-0505"))
    )
    (comp (ref "IC2")
      (value "LM1117-3.3")
      (footprint "eagle-import:TO252")
      (libsource (lib "eagle-import") (part "REG1117T"))
    )
    (comp (ref "IC6")
      (value "LM4040B10")
      (footprint "eagle-import:DBZ_R-PDSO-G3")
      (libsource (lib "eagle-import") (part "LM4041DBZB12"))
    )
    (comp (ref "IC7")
      (value "LM1117-3.3")
      (footprint "eagle-import:SOT223")
      (libsource (lib "eagle-import") (part "REG1117"))
    )
    (comp (ref "R11")
      (value "4.7")
      (footprint "eagle-import:R1206")
      (libsource (lib "eagle-import") (part "R-US_R1206"))
    )
    (comp (ref "R30")
      (value "470")
      (footprint "eagle-import:R0603")
      (libsource (lib "eagle-import") (part "R-US_R0603"))
    )
    (comp (ref "U$2")
      (value "EURO_POWER2")
      (footprint "eagle-import:EURO_POWER2")
      (libsource (lib "eagle-import") (part "EURO_POWER2"))
    )
    (comp (ref "C8")
      (value "100n")
      (footprint "eagle-import:C0603")
      (libsource (lib "eagle-import") (part "C-USC0603"))
    )
    (comp (ref "C12")
      (value "1u")
      (footprint "eagle-import:C0603K")
      (libsource (lib "eagle-import") (part "C-USC0603K"))
    )
    (comp (ref "C14")
      (value "100n")
      (footprint "eagle-import:C0603K")
      (libsource (lib "eagle-import") (part "C-USC0603K"))
    )
    (comp (ref "C17")
      (value "100n")
      (footprint "eagle-import:C0603K")
      (libsource (lib "eagle-import") (part "C-USC0603K"))
    )
    (comp (ref "C18")
      (value "100n")
      (footprint "eagle-import:C0603K")
      (libsource (lib "eagle-import") (part "C-USC0603K"))
    )
    (comp (ref "C19")
      (value "2.2u")
      (footprint "eagle-import:C0805K")
      (libsource (lib "eagle-import") (part "rcl@1_C-USC0805K"))
    )
    (comp (ref "C24")
      (value "2.2u")
      (footprint "eagle-import:C0805K")
      (libsource (lib "eagle-import") (part "rcl@1_C-USC0805K"))
    )
    (comp (ref "C25")
      (value "100n")
      (footprint "eagle-import:C0603K")
      (libsource (lib "eagle-import") (part "rcl@1_C-USC0603K"))
    )
    (comp (ref "C28")
      (value "10u")
      (footprint "eagle-import:153CLV-0405")
      (libsource (lib "eagle-import") (part "rcl@1_CPOL-US153CLV-0405"))
    )
    (comp (ref "C29")
      (value "100n")
      (footprint "eagle-import:C0603K")
      (libsource (lib "eagle-import") (part "C-USC0603K"))
    )
    (comp (ref "C30")
      (value "100n")
      (footprint "eagle-import:C0603K")
      (libsource (lib "eagle-import") (part "rcl@1_C-USC0603K"))
    )
    (comp (ref "C31")
      (value "10u")
      (footprint "eagle-import:PANASONIC_B")
      (libsource (lib "eagle-import") (part "CPOL-USB"))
    )
    (comp (ref "C32")
      (value "100n")
      (footprint "eagle-import:C0603")
      (libsource (lib "eagle-import") (part "C-USC0603"))
    )
    (comp (ref "C34")
      (value "100n")
      (footprint "eagle-import:C0603")
      (libsource (lib "eagle-import") (part "C-USC0603"))
    )
    (comp (ref "C35")
      (value "10u")
      (footprint "eagle-import:PANASONIC_B")
      (libsource (lib "eagle-import") (part "CPOL-USB"))
    )
    (comp (ref "C49")
      (value "10u")
      (footprint "eagle-import:PANASONIC_A")
      (libsource (lib "eagle-import") (part "CPOL-USA"))
    )
    (comp (ref "C50")
      (value "1u")
      (footprint "eagle-import:C0603K")
      (libsource (lib "eagle-import") (part "rcl@1_C-USC0603K"))
    )
    (comp (ref "IC5")
      (value "STM32F405RGT6")
      (footprint "eagle-import:TQFP-10X10-64")
      (libsource (lib "eagle-import") (part "STM32F20X"))
    )
    (comp (ref "IC8")
      (value "WM8731")
      (footprint "eagle-import:SSOP28")
      (libsource (lib "eagle-import") (part "WM8731"))
    )
    (comp (ref "JP2")
      (value "M05X2MINIJTAG")
      (footprint "eagle-import:2X5-1.27")
      (libsource (lib "eagle-import") (part "M05X2MINIJTAG"))
    )
    (comp (ref "Q3")
      (value "8MHz")
      (footprint "eagle-import:CRYSTAL_SMALLER")
      (libsource (lib "eagle-import") (part "CRYSTAL_SMALLER"))
    )
    (comp (ref "Q4")
      (value "12.288MHz")
      (footprint "eagle-import:CRYSTAL_SMALLER")
      (libsource (lib "eagle-import") (part "CRYSTAL_SMALLER"))
    )
    (comp (ref "R13")
      (value "10k")
      (footprint "eagle-import:PARTS_AMAN_RESISTOR_0603")
      (libsource (lib "eagle-import") (part "PARTS_AMAN_RESISTOR"))
    )
    (comp (ref "R17")
      (value "10k")
      (footprint "eagle-import:PARTS_AMAN_RESISTOR_0603")
      (libsource (lib "eagle-import") (part "PARTS_AMAN_RESISTOR"))
    )
    (comp (ref "R40")
      (value "2.2k")
      (footprint "eagle-import:PARTS_AMAN_RESISTOR_0603")
      (libsource (lib "eagle-import") (part "PARTS_AMAN_RESISTOR"))
    )
    (comp (ref "R41")
      (value "2.2k")
      (footprint "eagle-import:PARTS_AMAN_RESISTOR_0603")
      (libsource (lib "eagle-import") (part "PARTS_AMAN_RESISTOR"))
    )
    (comp (ref "U$4")
      (value "1X3_SMALL")
      (footprint "eagle-import:1X3_SMALL")
      (libsource (lib "eagle-import") (part "1X3_SMALL"))
    )
  )
  (nets
    (net (code "1") (name "+3V3") (class "Default")
      (node (ref "C17") (pin "1") (pinfunction "1_1") (pintype "passive"))
      (node (ref "C18") (pin "1") (pinfunction "1_1") (pintype "passive"))
      (node (ref "C25") (pin "1") (pinfunction "1_1") (pintype "passive"))
      (node (ref "C28") (pin "+") (pinfunction "+_+") (pintype "passive"))
      (node (ref "C29") (pin "1") (pinfunction "1_1") (pintype "passive"))
      (node (ref "C3") (pin "1") (pinfunction "1_1") (pintype "passive"))
      (node (ref "C30") (pin "1") (pinfunction "1_1") (pintype "passive"))
      (node (ref "C4") (pin "+") (pinfunction "+_+") (pintype "passive"))
      (node (ref "C5") (pin "1") (pinfunction "1_1") (pintype "passive"))
      (node (ref "C50") (pin "1") (pinfunction "1_1") (pintype "passive"))
      (node (ref "C8") (pin "1") (pinfunction "1_1") (pintype "passive"))
      (node (ref "IC11") (pin "10") (pinfunction "SCL_10") (pintype "input"))
      (node (ref "IC11") (pin "16") (pinfunction "VCC_16") (pintype "power_in"))
      (node (ref "IC2") (pin "3") (pinfunction "VOUT_3") (pintype "output"))
      (node (ref "IC5") (pin "19") (pinfunction "VDD_4_19") (pintype "power_in"))
      (node (ref "IC5") (pin "32") (pinfunction "VDD_1_32") (pintype "power_in"))
      (node (ref "IC5") (pin "48") (pinfunction "VDD_2_48") (pintype "power_in"))
      (node (ref "IC5") (pin "64") (pinfunction "VDD_3_64") (pintype "power_in"))
      (node (ref "IC8") (pin "1") (pinfunction "DBVDD_1") (pintype "bidirectional"))
      (node (ref "IC8") (pin "27") (pinfunction "DCVDD_27") (pintype "bidirectional"))
      (node (ref "JP2") (pin "1") (pinfunction "1_1") (pintype "passive"))
      (node (ref "R14") (pin "2") (pinfunction "2_2") (pintype "passive"))
      (node (ref "R16") (pin "2") (pinfunction "2_2") (pintype "passive"))
      (node (ref "R17") (pin "2") (pinfunction "2_2") (pintype "passive"))
      (node (ref "R40") (pin "2") (pinfunction "2_2") (pintype "passive"))
      (node (ref "R41") (pin "2") (pinfunction "2_2") (pintype "passive"))
    )
    (net (code "2") (name "+3V3_A") (class "Default")
      (node (ref "C12") (pin "1") (pinfunction "1_1") (pintype "passive"))
      (node (ref "C14") (pin "1") (pinfunction "1_1") (pintype "passive"))
      (node (ref "C15") (pin "1") (pinfunction "1_1") (pintype "passive"))
      (node (ref "C23") (pin "1") (pinfunction "1_1") (pintype "passive"))
      (node (ref "C26") (pin "1") (pinfunction "1_1") (pintype "passive"))
      (node (ref "C27") (pin "+") (pinfunction "+_+") (pintype "passive"))
      (node (ref "C31") (pin "+") (pinfunction "+_+") (pintype "passive"))
      (node (ref "C32") (pin "1") (pinfunction "1_1") (pintype "passive"))
      (node (ref "C49") (pin "+") (pinfunction "+_+") (pintype "passive"))
      (node (ref "C6") (pin "1") (pinfunction "1_1") (pintype "passive"))
      (node (ref "IC3") (pin "8") (pinfunction "V+_8") (pintype "power_in"))
      (node (ref "IC4") (pin "4") (pinfunction "V+_4") (pintype "power_in"))
      (node (ref "IC5") (pin "13") (pinfunction "VDDA_13") (pintype "power_in"))
      (node (ref "IC7") (pin "2") (pinfunction "VOUT_2") (pintype "output"))
      (node (ref "IC8") (pin "14") (pinfunction "AVDD_14") (pintype "bidirectional"))
      (node (ref "IC8") (pin "8") (pinfunction "HPVDD_8") (pintype "bidirectional"))
      (node (ref "JP37") (pin "1") (pinfunction "1_1") (pintype "passive"))
      (node (ref "JP41") (pin "1") (pinfunction "1_1") (pintype "passive"))
      (node (ref "U1") (pin "4") (pinfunction "V+_4") (pintype "power_in"))
    )
    (net (code "3") (name "AREF_-10") (class "Default")
      (node (ref "C16") (pin "1") (pinfunction "1_1") (pintype "passive"))
      (node (ref "IC6") (pin "2") (pinfunction "A_2") (pintype "passive"))
      (node (ref "JP14") (pin "1") (pinfunction "1_1") (pintype "passive"))
      (node (ref "JP40") (pin "1") (pinfunction "1_1") (pintype "passive"))
      (node (ref "R22") (pin "2") (pinfunction "2_2") (pintype "passive"))
      (node (ref "R23") (pin "2") (pinfunction "2_2") (pintype "passive"))
      (node (ref "R30") (pin "2") (pinfunction "2_2") (pintype "passive"))
      (node (ref "R36") (pin "2") (pinfunction "2_2") (pintype "passive"))
      (node (ref "R37") (pin "2") (pinfunction "2_2") (pintype "passive"))
    )
    (net (code "4") (name "BLEND_CV") (class "Default")
      (node (ref "C21") (pin "2") (pinfunction "2_2") (pintype "passive"))
      (node (ref "IC4") (pin "7") (pinfunction "OUT_7") (pintype "output"))
      (node (ref "IC5") (pin "21") (pinfunction "PA5/SPI1_SCK/ADC5/DAC2_21") (pintype "bidirectional"))
      (node (ref "R35") (pin "1") (pinfunction "1_1") (pintype "passive"))
    )
    (net (code "5") (name "BOOT_FLASH") (class "Default")
      (node (ref "IC5") (pin "60") (pinfunction "BOOT0_60") (pintype "bidirectional"))
      (node (ref "R13") (pin "2") (pinfunction "2_2") (pintype "passive"))
    )
    (net (code "6") (name "DENSITY_CV") (class "Default")
      (node (ref "C22") (pin "2") (pinfunction "2_2") (pintype "passive"))
      (node (ref "IC3") (pin "1") (pinfunction "OUT_1") (pintype "output"))
      (node (ref "IC5") (pin "17") (pinfunction "PA3/USART2_RX/ADC3/TIM2_CH4_17") (pintype "bidirectional"))
      (node (ref "R31") (pin "1") (pinfunction "1_1") (pintype "passive"))
    )
    (net (code "7") (name "GND") (class "Default")
      (node (ref "C1") (pin "-") (pinfunction "-_-") (pintype "passive"))
      (node (ref "C12") (pin "2") (pinfunction "2_2") (pintype "passive"))
      (node (ref "C13") (pin "+") (pinfunction "+_+") (pintype "passive"))
      (node (ref "C14") (pin "2") (pinfunction "2_2") (pintype "passive"))
      (node (ref "C15") (pin "2") (pinfunction "2_2") (pintype "passive"))
      (node (ref "C16") (pin "2") (pinfunction "2_2") (pintype "passive"))
      (node (ref "C17") (pin "2") (pinfunction "2_2") (pintype "passive"))
      (node (ref "C18") (pin "2") (pinfunction "2_2") (pintype "passive"))
      (node (ref "C19") (pin "2") (pinfunction "2_2") (pintype "passive"))
      (node (ref "C2") (pin "-") (pinfunction "-_-") (pintype "passive"))
      (node (ref "C23") (pin "2") (pinfunction "2_2") (pintype "passive"))
      (node (ref "C24") (pin "2") (pinfunction "2_2") (pintype "passive"))
      (node (ref "C25") (pin "2") (pinfunction "2_2") (pintype "passive"))
      (node (ref "C26") (pin "2") (pinfunction "2_2") (pintype "passive"))
      (node (ref "C27") (pin "-") (pinfunction "-_-") (pintype "passive"))
      (node (ref "C28") (pin "-") (pinfunction "-_-") (pintype "passive"))
      (node (ref "C29") (pin "2") (pinfunction "2_2") (pintype "passive"))
      (node (ref "C3") (pin "2") (pinfunction "2_2") (pintype "passive"))
      (node (ref "C30") (pin "2") (pinfunction "2_2") (pintype "passive"))
      (node (ref "C31") (pin "-") (pinfunction "-_-") (pintype "passive"))
      (node (ref "C32") (pin "2") (pinfunction "2_2") (pintype "passive"))
      (node (ref "C34") (pin "2") (pinfunction "2_2") (pintype "passive"))
      (node (ref "C35") (pin "-") (pinfunction "-_-") (pintype "passive"))
      (node (ref "C38") (pin "2") (pinfunction "2_2") (pintype "passive"))
      (node (ref "C39") (pin "2") (pinfunction "2_2") (pintype "passive"))
      (node (ref "C4") (pin "-") (pinfunction "-_-") (pintype "passive"))
      (node (ref "C43") (pin "2") (pinfunction "2_2") (pintype "passive"))
      (node (ref "C44") (pin "2") (pinfunction "2_2") (pintype "passive"))
      (node (ref "C45") (pin "1") (pinfunction "1_1") (pintype "passive"))
      (node (ref "C46") (pin "1") (pinfunction "1_1") (pintype "passive"))
      (node (ref "C49") (pin "-") (pinfunction "-_-") (pintype "passive"))
      (node (ref "C5") (pin "2") (pinfunction "2_2") (pintype "passive"))
      (node (ref "C50") (pin "2") (pinfunction "2_2") (pintype "passive"))
      (node (ref "C6") (pin "2") (pinfunction "2_2") (pintype "passive"))
      (node (ref "C8") (pin "2") (pinfunction "2_2") (pintype "passive"))
      (node (ref "IC10") (pin "3") (pinfunction "+IN_3") (pintype "input"))
      (node (ref "IC10") (pin "5") (pinfunction "+IN_5") (pintype "input"))
      (node (ref "IC11") (pin "13") (pinfunction "G_13") (pintype "input"))
      (node (ref "IC11") (pin "8") (pinfunction "GND_8") (pintype "power_in"))
      (node (ref "IC2") (pin "1") (pinfunction "GND_1") (pintype "power_in"))
      (node (ref "IC3") (pin "3") (pinfunction "+IN_3") (pintype "input"))
      (node (ref "IC3") (pin "4") (pinfunction "V-_4") (pintype "power_in"))
      (node (ref "IC3") (pin "5") (pinfunction "+IN_5") (pintype "input"))
      (node (ref "IC4") (pin "10") (pinfunction "+IN_10") (pintype "input"))
      (node (ref "IC4") (pin "11") (pinfunction "V-_11") (pintype "power_in"))
      (node (ref "IC4") (pin "12") (pinfunction "+IN_12") (pintype "input"))
      (node (ref "IC4") (pin "3") (pinfunction "+IN_3") (pintype "input"))
      (node (ref "IC4") (pin "5") (pinfunction "+IN_5") (pintype "input"))
      (node (ref "IC5") (pin "12") (pinfunction "VSSA_12") (pintype "power_in"))
      (node (ref "IC5") (pin "18") (pinfunction "VSS_4_18") (pintype "power_in"))
      (node (ref "IC5") (pin "26") (pinfunction "PB0/ADC8/TIM3_CH3_26") (pintype "bidirectional"))
      (node (ref "IC5") (pin "28") (pinfunction "PB2/BOOT1_28") (pintype "bidirectional"))
      (node (ref "IC5") (pin "63") (pinfunction "VSS_3_63") (pintype "power_in"))
      (node (ref "IC6") (pin "1") (pinfunction "C_1") (pintype "passive"))
      (node (ref "IC7") (pin "1") (pinfunction "GND_1") (pintype "power_in"))
      (node (ref "IC8") (pin "11") (pinfunction "HPGND_11") (pintype "bidirectional"))
      (node (ref "IC8") (pin "15") (pinfunction "AGND_15") (pintype "bidirectional"))
      (node (ref "IC8") (pin "21") (pinfunction "MODE_21") (pintype "bidirectional"))
      (node (ref "IC8") (pin "22") (pinfunction "CSB_22") (pintype "bidirectional"))
      (node (ref "IC8") (pin "28") (pinfunction "DGND_28") (pintype "bidirectional"))
      (node (ref "IC9") (pin "3") (pinfunction "+IN_3") (pintype "input"))
      (node (ref "IC9") (pin "5") (pinfunction "+IN_5") (pintype "input"))
      (node (ref "JP2") (pin "3") (pinfunction "3_3") (pintype "passive"))
      (node (ref "JP2") (pin "5") (pinfunction "5_5") (pintype "passive"))
      (node (ref "JP2") (pin "9") (pinfunction "9_9") (pintype "passive"))
      (node (ref "JP38") (pin "1") (pinfunction "1_1") (pintype "passive"))
      (node (ref "JP39") (pin "1") (pinfunction "1_1") (pintype "passive"))
      (node (ref "JP42") (pin "1") (pinfunction "1_1") (pintype "passive"))
      (node (ref "JP43") (pin "1") (pinfunction "1_1") (pintype "passive"))
      (node (ref "Q1") (pin "E") (pinfunction "E_E") (pintype "passive"))
      (node (ref "Q2") (pin "E") (pinfunction "E_E") (pintype "passive"))
      (node (ref "Q3") (pin "GND") (pinfunction "GND_GND") (pintype "bidirectional"))
      (node (ref "Q4") (pin "GND") (pinfunction "GND_GND") (pintype "bidirectional"))
      (node (ref "R13") (pin "1") (pinfunction "1_1") (pintype "passive"))
      (node (ref "R50") (pin "1") (pinfunction "1_1") (pintype "passive"))
      (node (ref "R54") (pin "1") (pinfunction "1_1") (pintype "passive"))
      (node (ref "R56") (pin "1") (pinfunction "1_1") (pintype "passive"))
      (node (ref "R59") (pin "1") (pinfunction "1_1") (pintype "passive"))
      (node (ref "U$2") (pin "GND1") (pinfunction "GND_GND1") (pintype "bidirectional"))
      (node (ref "U$2") (pin "GND2") (pinfunction "GND_GND2") (pintype "bidirectional"))
      (node (ref "U$2") (pin "GND3") (pinfunction "GND_GND3") (pintype "bidirectional"))
      (node (ref "U$2") (pin "GND4") (pinfunction "GND_GND4") (pintype "bidirectional"))
      (node (ref "U$2") (pin "GND5") (pinfunction "GND_GND5") (pintype "bidirectional"))
      (node (ref "U$2") (pin "GND6") (pinfunction "GND_GND6") (pintype "bidirectional"))
      (node (ref "U$4") (pin "3") (pinfunction "P$1_3") (pintype "bidirectional"))
      (node (ref "U1") (pin "10") (pinfunction "+IN_10") (pintype "input"))
      (node (ref "U1") (pin "11") (pinfunction "V-_11") (pintype "power_in"))
      (node (ref "U1") (pin "12") (pinfunction "+IN_12") (pintype "input"))
      (node (ref "U1") (pin "3") (pinfunction "+IN_3") (pintype "input"))
      (node (ref "U1") (pin "5") (pinfunction "+IN_5") (pintype "input"))
    )
    (net (code "8") (name "I2C_SCL") (class "Default")
      (node (ref "IC5") (pin "29") (pinfunction "PB10/SPI2_SCK/I2S_SCK/I2C2_SCL/USART3_TX_29") (pintype "bidirectional"))
      (node (ref "IC8") (pin "24") (pinfunction "SCLK_24") (pintype "bidirectional"))
      (node (ref "R40") (pin "1") (pinfunction "1_1") (pintype "passive"))
    )
    (net (code "9") (name "I2C_SDA") (class "Default")
      (node (ref "IC5") (pin "30") (pinfunction "PB11/I2C2_SDA/USART3_RX_30") (pintype "bidirectional"))
      (node (ref "IC8") (pin "23") (pinfunction "SDIN_23") (pintype "bidirectional"))
      (node (ref "R41") (pin "1") (pinfunction "1_1") (pintype "passive"))
    )
    (net (code "10") (name "I2S_LRCK") (class "Default")
      (node (ref "IC5") (pin "33") (pinfunction "PB12/SPI2_NSS/I2S2_WS/I2C2_SMBA/USART3_CK/TIM1_BKIN_33") (pintype "bidirectional"))
      (node (ref "IC8") (pin "5") (pinfunction "DACLRC_5") (pintype "bidirectional"))
      (node (ref "IC8") (pin "7") (pinfunction "ADCLRC_7") (pintype "bidirectional"))
    )
    (net (code "11") (name "I2S_SCK") (class "Default")
      (node (ref "IC5") (pin "34") (pinfunction "PB13/SPI2_SCK/I2S2_SCK/USART3_CTS/TIM1_CH1N_34") (pintype "bidirectional"))
      (node (ref "IC8") (pin "3") (pinfunction "BCLK_3") (pintype "bidirectional"))
    )
    (net (code "12") (name "I2S_SIN") (class "Default")
      (node (ref "IC5") (pin "35") (pinfunction "PB14/SPI2_MISO/USART3_RTS/TIM1_CH2N_35") (pintype "bidirectional"))
      (node (ref "IC8") (pin "6") (pinfunction "ADCDAT_6") (pintype "bidirectional"))
    )
    (net (code "13") (name "I2S_SOUT") (class "Default")
      (node (ref "IC5") (pin "36") (pinfunction "PB15/SPI2_MOSI/I2S2_SD/TIM1_CH3N_36") (pintype "bidirectional"))
      (node (ref "IC8") (pin "4") (pinfunction "DACDAT_4") (pintype "bidirectional"))
    )
    (net (code "14") (name "JTCK") (class "Default")
      (node (ref "IC5") (pin "49") (pinfunction "PA14/JTCK-SWCLK_49") (pintype "bidirectional"))
      (node (ref "JP2") (pin "4") (pinfunction "4_4") (pintype "passive"))
    )
    (net (code "15") (name "JTDI") (class "Default")
      (node (ref "IC5") (pin "50") (pinfunction "PA15/JTDI/SPI3_NSS/I2S3_WS_50") (pintype "bidirectional"))
      (node (ref "JP2") (pin "8") (pinfunction "8_8") (pintype "passive"))
    )
    (net (code "16") (name "JTDO") (class "Default")
      (node (ref "IC5") (pin "55") (pinfunction "PB3/JTDO/SPI3_SCK/I2S3_SCK_55") (pintype "bidirectional"))
      (node (ref "JP2") (pin "6") (pinfunction "6_6") (pintype "passive"))
    )
    (net (code "17") (name "JTMS") (class "Default")
      (node (ref "IC5") (pin "46") (pinfunction "PA13/JTMS-SWDAT_46") (pintype "bidirectional"))
      (node (ref "JP2") (pin "2") (pinfunction "2_2") (pintype "passive"))
    )
    (net (code "18") (name "LED_DATA") (class "Default")
      (node (ref "IC11") (pin "14") (pinfunction "SER_14") (pintype "input"))
      (node (ref "IC5") (pin "57") (pinfunction "PB5/I2C1_SMBA/SPI1_MOSI/SPI3_MOSI/I2S3_SD_57") (pintype "bidirectional"))
    )
    (net (code "19") (name "LED_EN") (class "Default")
      (node (ref "IC11") (pin "12") (pinfunction "RCK_12") (pintype "input"))
      (node (ref "IC5") (pin "24") (pinfunction "PC4/ADC14_24") (pintype "bidirectional"))
    )
    (net (code "20") (name "LED_REC") (class "Default")
      (node (ref "IC5") (pin "62") (pinfunction "PB9/SPI2_NSS/I2S2_WS/I2C1_SDA/TIM4_CH4_62") (pintype "bidirectional"))
      (node (ref "JP21") (pin "1") (pinfunction "1_1") (pintype "passive"))
    )
    (net (code "21") (name "LED_SCK") (class "Default")
      (node (ref "IC11") (pin "11") (pinfunction "SCK_11") (pintype "input"))
      (node (ref "IC5") (pin "25") (pinfunction "PC5/ADC15_25") (pintype "bidirectional"))
    )
    (net (code "22") (name "LIN") (class "Default")
      (node (ref "C37") (pin "+") (pinfunction "+_+") (pintype "passive"))
      (node (ref "IC8") (pin "20") (pinfunction "LLINEIN_20") (pintype "bidirectional"))
    )
    (net (code "23") (name "LOUT") (class "Default")
      (node (ref "C33") (pin "+") (pinfunction "+_+") (pintype "passive"))
      (node (ref "IC8") (pin "12") (pinfunction "LOUT_12") (pintype "bidirectional"))
    )
    (net (code "24") (name "Net-(BR1-~{_1})") (class "Default")
      (node (ref "BR1") (pin "3") (pinfunction "~{_1}_3") (pintype "bidirectional"))
      (node (ref "U$2") (pin "V+") (pinfunction "V++_V+") (pintype "bidirectional"))
      (node (ref "U$2") (pin "V++") (pinfunction "V++_V++") (pintype "bidirectional"))
    )
    (net (code "25") (name "Net-(BR1-~{_2})") (class "Default")
      (node (ref "BR1") (pin "4") (pinfunction "~{_2}_4") (pintype "bidirectional"))
      (node (ref "U$2") (pin "V-") (pinfunction "V--_V-") (pintype "bidirectional"))
      (node (ref "U$2") (pin "V--") (pinfunction "V--_V--") (pintype "bidirectional"))
    )
    (net (code "26") (name "Net-(C33-Pad-)") (class "Default")
      (node (ref "C33") (pin "-") (pinfunction "-_-") (pintype "passive"))
      (node (ref "R51") (pin "2") (pinfunction "2_2") (pintype "passive"))
      (node (ref "R59") (pin "2") (pinfunction "2_2") (pintype "passive"))
    )
    (net (code "27") (name "Net-(C36-Pad-)") (class "Default")
      (node (ref "C36") (pin "-") (pinfunction "-_-") (pintype "passive"))
      (node (ref "C43") (pin "1") (pinfunction "1_1") (pintype "passive"))
      (node (ref "R53") (pin "1") (pinfunction "1_1") (pintype "passive"))
      (node (ref "R54") (pin "2") (pinfunction "2_2") (pintype "passive"))
    )
    (net (code "28") (name "Net-(C37-Pad-)") (class "Default")
      (node (ref "C37") (pin "-") (pinfunction "-_-") (pintype "passive"))
      (node (ref "C44") (pin "1") (pinfunction "1_1") (pintype "passive"))
      (node (ref "R55") (pin "1") (pinfunction "1_1") (pintype "passive"))
      (node (ref "R56") (pin "2") (pinfunction "2_2") (pintype "passive"))
    )
    (net (code "29") (name "Net-(C41-Pad-)") (class "Default")
      (node (ref "C41") (pin "-") (pinfunction "-_-") (pintype "passive"))
      (node (ref "R50") (pin "2") (pinfunction "2_2") (pintype "passive"))
      (node (ref "R52") (pin "2") (pinfunction "2_2") (pintype "passive"))
    )
    (net (code "30") (name "Net-(IC2-VIN)") (class "Default")
      (node (ref "C2") (pin "+") (pinfunction "+_+") (pintype "passive"))
      (node (ref "IC2") (pin "2") (pinfunction "VIN_2") (pintype "input"))
      (node (ref "R11") (pin "2") (pinfunction "2_2") (pintype "passive"))
    )
    (net (code "31") (name "Net-(IC3A--IN)") (class "Default")
      (node (ref "C22") (pin "1") (pinfunction "1_1") (pintype "passive"))
      (node (ref "IC3") (pin "2") (pinfunction "-IN_2") (pintype "input"))
      (node (ref "R31") (pin "2") (pinfunction "2_2") (pintype "passive"))
      (node (ref "R32") (pin "1") (pinfunction "1_1") (pintype "passive"))
      (node (ref "R33") (pin "1") (pinfunction "1_1") (pintype "passive"))
    )
    (net (code "32") (name "Net-(IC3B--IN)") (class "Default")
      (node (ref "C9") (pin "1") (pinfunction "1_1") (pintype "passive"))
      (node (ref "IC3") (pin "6") (pinfunction "-IN_6") (pintype "input"))
      (node (ref "R27") (pin "2") (pinfunction "2_2") (pintype "passive"))
      (node (ref "R28") (pin "1") (pinfunction "1_1") (pintype "passive"))
      (node (ref "R29") (pin "1") (pinfunction "1_1") (pintype "passive"))
    )
    (net (code "33") (name "Net-(IC4A--IN)") (class "Default")
      (node (ref "C20") (pin "1") (pinfunction "1_1") (pintype "passive"))
      (node (ref "IC4") (pin "2") (pinfunction "-IN_2") (pintype "input"))
      (node (ref "R34") (pin "2") (pinfunction "2_2") (pintype "passive"))
      (node (ref "R36") (pin "1") (pinfunction "1_1") (pintype "passive"))
      (node (ref "R38") (pin "1") (pinfunction "1_1") (pintype "passive"))
    )
    (net (code "34") (name "Net-(IC4B--IN)") (class "Default")
      (node (ref "C21") (pin "1") (pinfunction "1_1") (pintype "passive"))
      (node (ref "IC4") (pin "6") (pinfunction "-IN_6") (pintype "input"))
      (node (ref "R35") (pin "2") (pinfunction "2_2") (pintype "passive"))
      (node (ref "R37") (pin "1") (pinfunction "1_1") (pintype "passive"))
      (node (ref "R39") (pin "1") (pinfunction "1_1") (pintype "passive"))
    )
    (net (code "35") (name "Net-(IC4C--IN)") (class "Default")
      (node (ref "C11") (pin "1") (pinfunction "1_1") (pintype "passive"))
      (node (ref "IC4") (pin "9") (pinfunction "-IN_9") (pintype "input"))
      (node (ref "R23") (pin "1") (pinfunction "1_1") (pintype "passive"))
      (node (ref "R24") (pin "1") (pinfunction "1_1") (pintype "passive"))
      (node (ref "R26") (pin "2") (pinfunction "2_2") (pintype "passive"))
    )
    (net (code "36") (name "Net-(IC4D--IN)") (class "Default")
      (node (ref "C10") (pin "1") (pinfunction "1_1") (pintype "passive"))
      (node (ref "IC4") (pin "13") (pinfunction "-IN_13") (pintype "input"))
      (node (ref "R21") (pin "1") (pinfunction "1_1") (pintype "passive"))
      (node (ref "R22") (pin "1") (pinfunction "1_1") (pintype "passive"))
      (node (ref "R25") (pin "2") (pinfunction "2_2") (pintype "passive"))
    )
    (net (code "37") (name "Net-(IC5-PD0{slash}OSC_IN)") (class "Default")
      (node (ref "IC5") (pin "5") (pinfunction "PD0/OSC_IN_5") (pintype "bidirectional"))
      (node (ref "Q3") (pin "X2") (pinfunction "X2_X2") (pintype "bidirectional"))
    )
    (net (code "38") (name "Net-(IC5-PD1{slash}OSC_OUT)") (class "Default")
      (node (ref "IC5") (pin "6") (pinfunction "PD1/OSC_OUT_6") (pintype "bidirectional"))
      (node (ref "Q3") (pin "X1") (pinfunction "X1_X1") (pintype "bidirectional"))
    )
    (net (code "39") (name "Net-(IC5-VCAP_1)") (class "Default")
      (node (ref "C24") (pin "1") (pinfunction "1_1") (pintype "passive"))
      (node (ref "IC5") (pin "31") (pinfunction "VCAP_1_31") (pintype "power_in"))
    )
    (net (code "40") (name "Net-(IC5-VCAP_2)") (class "Default")
      (node (ref "C19") (pin "1") (pinfunction "1_1") (pintype "passive"))
      (node (ref "IC5") (pin "47") (pinfunction "VCAP_2_47") (pintype "power_in"))
    )
    (net (code "41") (name "Net-(IC8-VMID)") (class "Default")
      (node (ref "C34") (pin "1") (pinfunction "1_1") (pintype "passive"))
      (node (ref "C35") (pin "+") (pinfunction "+_+") (pintype "passive"))
      (node (ref "IC8") (pin "16") (pinfunction "VMID_16") (pintype "bidirectional"))
    )
    (net (code "42") (name "Net-(IC8-XTI{slash}MCLK)") (class "Default")
      (node (ref "IC8") (pin "25") (pinfunction "XTI/MCLK_25") (pintype "bidirectional"))
      (node (ref "Q4") (pin "X1") (pinfunction "X1_X1") (pintype "bidirectional"))
    )
    (net (code "43") (name "Net-(IC8-XTO)") (class "Default")
      (node (ref "IC8") (pin "26") (pinfunction "XTO_26") (pintype "bidirectional"))
      (node (ref "Q4") (pin "X2") (pinfunction "X2_X2") (pintype "bidirectional"))
    )
    (net (code "44") (name "Net-(IC9A--IN)") (class "Default")
      (node (ref "IC9") (pin "2") (pinfunction "-IN_2") (pintype "input"))
      (node (ref "R46") (pin "2") (pinfunction "2_2") (pintype "passive"))
      (node (ref "R57") (pin "1") (pinfunction "1_1") (pintype "passive"))
    )
    (net (code "45") (name "Net-(IC9A-OUT)") (class "Default")
      (node (ref "IC9") (pin "1") (pinfunction "OUT_1") (pintype "output"))
      (node (ref "JP17") (pin "1") (pinfunction "1_1") (pintype "passive"))
      (node (ref "R55") (pin "2") (pinfunction "2_2") (pintype "passive"))
    )
    (net (code "46") (name "Net-(IC9B--IN)") (class "Default")
      (node (ref "IC9") (pin "6") (pinfunction "-IN_6") (pintype "input"))
      (node (ref "R47") (pin "2") (pinfunction "2_2") (pintype "passive"))
      (node (ref "R58") (pin "1") (pinfunction "1_1") (pintype "passive"))
    )
    (net (code "47") (name "Net-(IC9B-OUT)") (class "Default")
      (node (ref "IC9") (pin "7") (pinfunction "OUT_7") (pintype "output"))
      (node (ref "JP18") (pin "1") (pinfunction "1_1") (pintype "passive"))
      (node (ref "R53") (pin "2") (pinfunction "2_2") (pintype "passive"))
    )
    (net (code "48") (name "Net-(IC10A--IN)") (class "Default")
      (node (ref "C40") (pin "1") (pinfunction "1_1") (pintype "passive"))
      (node (ref "IC10") (pin "2") (pinfunction "-IN_2") (pintype "input"))
      (node (ref "R49") (pin "2") (pinfunction "2_2") (pintype "passive"))
      (node (ref "R51") (pin "1") (pinfunction "1_1") (pintype "passive"))
    )
    (net (code "49") (name "Net-(IC10A-OUT)") (class "Default")
      (node (ref "C40") (pin "2") (pinfunction "2_2") (pintype "passive"))
      (node (ref "IC10") (pin "1") (pinfunction "OUT_1") (pintype "output"))
      (node (ref "R49") (pin "1") (pinfunction "1_1") (pintype "passive"))
      (node (ref "R61") (pin "2") (pinfunction "2_2") (pintype "passive"))
    )
    (net (code "50") (name "Net-(IC10B--IN)") (class "Default")
      (node (ref "C42") (pin "1") (pinfunction "1_1") (pintype "passive"))
      (node (ref "IC10") (pin "6") (pinfunction "-IN_6") (pintype "input"))
      (node (ref "R48") (pin "2") (pinfunction "2_2") (pintype "passive"))
      (node (ref "R52") (pin "1") (pinfunction "1_1") (pintype "passive"))
    )
    (net (code "51") (name "Net-(IC10B-OUT)") (class "Default")
      (node (ref "C42") (pin "2") (pinfunction "2_2") (pintype "passive"))
      (node (ref "IC10") (pin "7") (pinfunction "OUT_7") (pintype "output"))
      (node (ref "R48") (pin "1") (pinfunction "1_1") (pintype "passive"))
      (node (ref "R62") (pin "2") (pinfunction "2_2") (pintype "passive"))
    )
    (net (code "52") (name "Net-(IC11-QA)") (class "Default")
      (node (ref "IC11") (pin "15") (pinfunction "QA_15") (pintype "tri_state"))
      (node (ref "JP23") (pin "1") (pinfunction "1_1") (pintype "passive"))
    )
    (net (code "53") (name "Net-(IC11-QB)") (class "Default")
      (node (ref "IC11") (pin "1") (pinfunction "QB_1") (pintype "tri_state"))
      (node (ref "JP24") (pin "1") (pinfunction "1_1") (pintype "passive"))
    )
    (net (code "54") (name "Net-(IC11-QC)") (class "Default")
      (node (ref "IC11") (pin "2") (pinfunction "QC_2") (pintype "tri_state"))
      (node (ref "JP25") (pin "1") (pinfunction "1_1") (pintype "passive"))
    )
    (net (code "55") (name "Net-(IC11-QD)") (class "Default")
      (node (ref "IC11") (pin "3") (pinfunction "QD_3") (pintype "tri_state"))
      (node (ref "JP26") (pin "1") (pinfunction "1_1") (pintype "passive"))
    )
    (net (code "56") (name "Net-(IC11-QE)") (class "Default")
      (node (ref "IC11") (pin "4") (pinfunction "QE_4") (pintype "tri_state"))
      (node (ref "JP27") (pin "1") (pinfunction "1_1") (pintype "passive"))
    )
    (net (code "57") (name "Net-(IC11-QF)") (class "Default")
      (node (ref "IC11") (pin "5") (pinfunction "QF_5") (pintype "tri_state"))
      (node (ref "JP28") (pin "1") (pinfunction "1_1") (pintype "passive"))
    )
    (net (code "58") (name "Net-(IC11-QG)") (class "Default")
      (node (ref "IC11") (pin "6") (pinfunction "QG_6") (pintype "tri_state"))
      (node (ref "JP29") (pin "1") (pinfunction "1_1") (pintype "passive"))
    )
    (net (code "59") (name "Net-(IC11-QH)") (class "Default")
      (node (ref "IC11") (pin "7") (pinfunction "QH_7") (pintype "tri_state"))
      (node (ref "JP30") (pin "1") (pinfunction "1_1") (pintype "passive"))
    )
    (net (code "60") (name "Net-(JP1-Pad1)") (class "Default")
      (node (ref "JP1") (pin "1") (pinfunction "1_1") (pintype "passive"))
      (node (ref "R46") (pin "1") (pinfunction "1_1") (pintype "passive"))
    )
    (net (code "61") (name "Net-(JP3-Pad1)") (class "Default")
      (node (ref "JP3") (pin "1") (pinfunction "1_1") (pintype "passive"))
      (node (ref "R47") (pin "1") (pinfunction "1_1") (pintype "passive"))
    )
    (net (code "62") (name "Net-(JP4-Pad1)") (class "Default")
      (node (ref "JP4") (pin "1") (pinfunction "1_1") (pintype "passive"))
      (node (ref "R58") (pin "2") (pinfunction "2_2") (pintype "passive"))
    )
    (net (code "63") (name "Net-(JP5-Pad1)") (class "Default")
      (node (ref "JP5") (pin "1") (pinfunction "1_1") (pintype "passive"))
      (node (ref "R57") (pin "2") (pinfunction "2_2") (pintype "passive"))
    )
    (net (code "64") (name "Net-(JP6-Pad1)") (class "Default")
      (node (ref "JP6") (pin "1") (pinfunction "1_1") (pintype "passive"))
      (node (ref "R29") (pin "2") (pinfunction "2_2") (pintype "passive"))
    )
    (net (code "65") (name "Net-(JP7-Pad1)") (class "Default")
      (node (ref "JP7") (pin "1") (pinfunction "1_1") (pintype "passive"))
      (node (ref "R32") (pin "2") (pinfunction "2_2") (pintype "passive"))
    )
    (net (code "66") (name "Net-(JP8-Pad1)") (class "Default")
      (node (ref "JP8") (pin "1") (pinfunction "1_1") (pintype "passive"))
      (node (ref "R38") (pin "2") (pinfunction "2_2") (pintype "passive"))
    )
    (net (code "67") (name "Net-(JP9-Pad1)") (class "Default")
      (node (ref "JP9") (pin "1") (pinfunction "1_1") (pintype "passive"))
      (node (ref "R21") (pin "2") (pinfunction "2_2") (pintype "passive"))
    )
    (net (code "68") (name "Net-(JP10-Pad1)") (class "Default")
      (node (ref "JP10") (pin "1") (pinfunction "1_1") (pintype "passive"))
      (node (ref "R39") (pin "2") (pinfunction "2_2") (pintype "passive"))
    )
    (net (code "69") (name "Net-(JP11-Pad1)") (class "Default")
      (node (ref "JP11") (pin "1") (pinfunction "1_1") (pintype "passive"))
      (node (ref "R24") (pin "2") (pinfunction "2_2") (pintype "passive"))
    )
    (net (code "70") (name "Net-(JP12-Pad1)") (class "Default")
      (node (ref "JP12") (pin "1") (pinfunction "1_1") (pintype "passive"))
      (node (ref "R62") (pin "1") (pinfunction "1_1") (pintype "passive"))
    )
    (net (code "71") (name "Net-(JP13-Pad1)") (class "Default")
      (node (ref "JP13") (pin "1") (pinfunction "1_1") (pintype "passive"))
      (node (ref "R61") (pin "1") (pinfunction "1_1") (pintype "passive"))
    )
    (net (code "72") (name "Net-(JP15-Pad1)") (class "Default")
      (node (ref "JP15") (pin "1") (pinfunction "1_1") (pintype "passive"))
      (node (ref "R28") (pin "2") (pinfunction "2_2") (pintype "passive"))
    )
    (net (code "73") (name "Net-(JP16-Pad1)") (class "Default")
      (node (ref "JP16") (pin "1") (pinfunction "1_1") (pintype "passive"))
      (node (ref "R33") (pin "2") (pinfunction "2_2") (pintype "passive"))
    )
    (net (code "74") (name "Net-(JP19-Pad1)") (class "Default")
      (node (ref "JP19") (pin "1") (pinfunction "1_1") (pintype "passive"))
      (node (ref "R12") (pin "1") (pinfunction "1_1") (pintype "passive"))
    )
    (net (code "75") (name "Net-(JP20-Pad1)") (class "Default")
      (node (ref "JP20") (pin "1") (pinfunction "1_1") (pintype "passive"))
      (node (ref "R15") (pin "1") (pinfunction "1_1") (pintype "passive"))
    )
    (net (code "76") (name "Net-(JP45-Pad1)") (class "Default")
      (node (ref "JP45") (pin "1") (pinfunction "1_1") (pintype "passive"))
      (node (ref "R2") (pin "1") (pinfunction "1_1") (pintype "passive"))
    )
    (net (code "77") (name "Net-(JP46-Pad1)") (class "Default")
      (node (ref "JP46") (pin "1") (pinfunction "1_1") (pintype "passive"))
      (node (ref "R1") (pin "1") (pinfunction "1_1") (pintype "passive"))
    )
    (net (code "78") (name "Net-(JP47-Pad1)") (class "Default")
      (node (ref "JP47") (pin "1") (pinfunction "1_1") (pintype "passive"))
      (node (ref "R5") (pin "1") (pinfunction "1_1") (pintype "passive"))
    )
    (net (code "79") (name "Net-(JP48-Pad1)") (class "Default")
      (node (ref "JP48") (pin "1") (pinfunction "1_1") (pintype "passive"))
      (node (ref "R4") (pin "1") (pinfunction "1_1") (pintype "passive"))
    )
    (net (code "80") (name "Net-(JP49-Pad1)") (class "Default")
      (node (ref "JP49") (pin "1") (pinfunction "1_1") (pintype "passive"))
      (node (ref "R7") (pin "1") (pinfunction "1_1") (pintype "passive"))
    )
    (net (code "81") (name "Net-(JP50-Pad1)") (class "Default")
      (node (ref "JP50") (pin "1") (pinfunction "1_1") (pintype "passive"))
      (node (ref "R8") (pin "1") (pinfunction "1_1") (pintype "passive"))
    )
    (net (code "82") (name "Net-(Q1-PadB)") (class "Default")
      (node (ref "Q1") (pin "B") (pinfunction "B_B") (pintype "passive"))
      (node (ref "R12") (pin "2") (pinfunction "2_2") (pintype "passive"))
    )
    (net (code "83") (name "Net-(Q2-PadB)") (class "Default")
      (node (ref "Q2") (pin "B") (pinfunction "B_B") (pintype "passive"))
      (node (ref "R15") (pin "2") (pinfunction "2_2") (pintype "passive"))
    )
    (net (code "84") (name "Net-(U1A--IN)") (class "Default")
      (node (ref "C7") (pin "1") (pinfunction "1_1") (pintype "passive"))
      (node (ref "R1") (pin "2") (pinfunction "2_2") (pintype "passive"))
      (node (ref "R2") (pin "2") (pinfunction "2_2") (pintype "passive"))
      (node (ref "R3") (pin "1") (pinfunction "1_1") (pintype "passive"))
      (node (ref "U1") (pin "2") (pinfunction "-IN_2") (pintype "input"))
    )
    (net (code "85") (name "Net-(U1B--IN)") (class "Default")
      (node (ref "C47") (pin "1") (pinfunction "1_1") (pintype "passive"))
      (node (ref "R4") (pin "2") (pinfunction "2_2") (pintype "passive"))
      (node (ref "R5") (pin "2") (pinfunction "2_2") (pintype "passive"))
      (node (ref "R6") (pin "1") (pinfunction "1_1") (pintype "passive"))
      (node (ref "U1") (pin "6") (pinfunction "-IN_6") (pintype "input"))
    )
    (net (code "86") (name "Net-(U1C--IN)") (class "Default")
      (node (ref "C48") (pin "1") (pinfunction "1_1") (pintype "passive"))
      (node (ref "R7") (pin "2") (pinfunction "2_2") (pintype "passive"))
      (node (ref "R8") (pin "2") (pinfunction "2_2") (pintype "passive"))
      (node (ref "R9") (pin "1") (pinfunction "1_1") (pintype "passive"))
      (node (ref "U1") (pin "9") (pinfunction "-IN_9") (pintype "input"))
    )
    (net (code "87") (name "Net-(U1D--IN)") (class "Default")
      (node (ref "U1") (pin "13") (pinfunction "-IN_13") (pintype "input"))
      (node (ref "U1") (pin "14") (pinfunction "OUT_14") (pintype "output"))
    )
    (net (code "88") (name "PARAM_2") (class "Default")
      (node (ref "C7") (pin "2") (pinfunction "2_2") (pintype "passive"))
      (node (ref "IC5") (pin "27") (pinfunction "PB1/ADC9/TIM3_CH4_27") (pintype "bidirectional"))
      (node (ref "R3") (pin "2") (pinfunction "2_2") (pintype "passive"))
      (node (ref "U1") (pin "1") (pinfunction "OUT_1") (pintype "output"))
    )
    (net (code "89") (name "PARAM_3") (class "Default")
      (node (ref "C47") (pin "2") (pinfunction "2_2") (pintype "passive"))
      (node (ref "IC5") (pin "10") (pinfunction "PC2/SPI2_MISO/ADC12_10") (pintype "bidirectional"))
      (node (ref "R6") (pin "2") (pinfunction "2_2") (pintype "passive"))
      (node (ref "U1") (pin "7") (pinfunction "OUT_7") (pintype "output"))
    )
    (net (code "90") (name "PARAM_4") (class "Default")
      (node (ref "C48") (pin "2") (pinfunction "2_2") (pintype "passive"))
      (node (ref "IC5") (pin "11") (pinfunction "PC3/SPI2_MOSI/I2S2_SD/ADC13_11") (pintype "bidirectional"))
      (node (ref "R9") (pin "2") (pinfunction "2_2") (pintype "passive"))
      (node (ref "U1") (pin "8") (pinfunction "OUT_8") (pintype "output"))
    )
    (net (code "91") (name "PITCH_POT") (class "Default")
      (node (ref "IC5") (pin "9") (pinfunction "PC1/ADC11_9") (pintype "bidirectional"))
      (node (ref "JP33") (pin "1") (pinfunction "1_1") (pintype "passive"))
    )
    (net (code "92") (name "PLAY") (class "Default")
      (node (ref "IC5") (pin "58") (pinfunction "PB6/I2C1_SCL/TIM4_CH1/USART1_TX_58") (pintype "bidirectional"))
      (node (ref "Q2") (pin "C") (pinfunction "C_C") (pintype "passive"))
      (node (ref "R16") (pin "1") (pinfunction "1_1") (pintype "passive"))
    )
    (net (code "93") (name "POSITION_POT_CV") (class "Default")
      (node (ref "C9") (pin "2") (pinfunction "2_2") (pintype "passive"))
      (node (ref "IC3") (pin "7") (pinfunction "OUT_7") (pintype "output"))
      (node (ref "IC5") (pin "16") (pinfunction "PA2/USART2_TX/ADC2/TIM2_CH3_16") (pintype "bidirectional"))
      (node (ref "R27") (pin "1") (pinfunction "1_1") (pintype "passive"))
    )
    (net (code "94") (name "POT_PARAM_1") (class "Default")
      (node (ref "IC5") (pin "23") (pinfunction "PA7/SPI1_MOSI/ADC7/TIM3_CH2_23") (pintype "bidirectional"))
      (node (ref "JP34") (pin "1") (pinfunction "1_1") (pintype "passive"))
    )
    (net (code "95") (name "REC") (class "Default")
      (node (ref "IC5") (pin "59") (pinfunction "PB7/I2C1_SDA/TIM4_CH2/USART1_RX_59") (pintype "bidirectional"))
      (node (ref "Q1") (pin "C") (pinfunction "C_C") (pintype "passive"))
      (node (ref "R14") (pin "1") (pinfunction "1_1") (pintype "passive"))
    )
    (net (code "96") (name "RESET") (class "Default")
      (node (ref "IC5") (pin "7") (pinfunction "NRST_7") (pintype "bidirectional"))
      (node (ref "JP2") (pin "10") (pinfunction "10_10") (pintype "passive"))
      (node (ref "R17") (pin "1") (pinfunction "1_1") (pintype "passive"))
    )
    (net (code "97") (name "RIN") (class "Default")
      (node (ref "C36") (pin "+") (pinfunction "+_+") (pintype "passive"))
      (node (ref "IC8") (pin "19") (pinfunction "RLINEIN_19") (pintype "bidirectional"))
    )
    (net (code "98") (name "ROUT") (class "Default")
      (node (ref "C41") (pin "+") (pinfunction "+_+") (pintype "passive"))
      (node (ref "IC8") (pin "13") (pinfunction "ROUT_13") (pintype "bidirectional"))
    )
    (net (code "99") (name "RX") (class "Default")
      (node (ref "IC5") (pin "43") (pinfunction "PA10/USART1_RX/TIM1_CH3_43") (pintype "bidirectional"))
      (node (ref "U$4") (pin "2") (pinfunction "P$1_2") (pintype "bidirectional"))
    )
    (net (code "100") (name "SIZE_CV") (class "Default")
      (node (ref "C10") (pin "2") (pinfunction "2_2") (pintype "passive"))
      (node (ref "IC4") (pin "14") (pinfunction "OUT_14") (pintype "output"))
      (node (ref "IC5") (pin "15") (pinfunction "PA1/USART2_RTS/UART4_RX/ADC1/TIM2_CH2_15") (pintype "bidirectional"))
      (node (ref "R25") (pin "1") (pinfunction "1_1") (pintype "passive"))
    )
    (net (code "101") (name "SIZE_POT") (class "Default")
      (node (ref "IC5") (pin "8") (pinfunction "PC0/ADC10_8") (pintype "bidirectional"))
      (node (ref "JP31") (pin "1") (pinfunction "1_1") (pintype "passive"))
    )
    (net (code "102") (name "SW_LOAD") (class "Default")
      (node (ref "IC5") (pin "51") (pinfunction "PC10/SPI3_SCK/I2S3_SCK/UART4_TX_51") (pintype "bidirectional"))
      (node (ref "JP36") (pin "1") (pinfunction "1_1") (pintype "passive"))
    )
    (net (code "103") (name "SW_MODE") (class "Default")
      (node (ref "IC5") (pin "52") (pinfunction "PC11/UART4_RX/SPI3_MISO/USART3_RX_52") (pintype "bidirectional"))
      (node (ref "JP35") (pin "1") (pinfunction "1_1") (pintype "passive"))
    )
    (net (code "104") (name "SW_REC") (class "Default")
      (node (ref "IC5") (pin "61") (pinfunction "PB8/TIM4_CH3/I2C1_SCL_61") (pintype "bidirectional"))
      (node (ref "JP22") (pin "1") (pinfunction "1_1") (pintype "passive"))
    )
    (net (code "105") (name "TEXTURE_CV") (class "Default")
      (node (ref "C11") (pin "2") (pinfunction "2_2") (pintype "passive"))
      (node (ref "IC4") (pin "8") (pinfunction "OUT_8") (pintype "output"))
      (node (ref "IC5") (pin "14") (pinfunction "PA0-WKUP/USART2_CTS/UART4_TX/ADC0/TIM2_CH1_ETR_14") (pintype "bidirectional"))
      (node (ref "R26") (pin "1") (pinfunction "1_1") (pintype "passive"))
    )
    (net (code "106") (name "TEXTURE_POT") (class "Default")
      (node (ref "IC5") (pin "22") (pinfunction "PA6/SPI1_MISO/ADC6/TIM3_CH1_22") (pintype "bidirectional"))
      (node (ref "JP32") (pin "1") (pinfunction "1_1") (pintype "passive"))
    )
    (net (code "107") (name "TX") (class "Default")
      (node (ref "IC5") (pin "42") (pinfunction "PA9/USART1_TX/TIM1_CH2_42") (pintype "bidirectional"))
      (node (ref "U$4") (pin "1") (pinfunction "P$1_1") (pintype "bidirectional"))
    )
    (net (code "108") (name "VBAT") (class "Default")
      (node (ref "IC5") (pin "1") (pinfunction "VBAT_1") (pintype "power_in"))
    )
    (net (code "109") (name "VCC") (class "Default")
      (node (ref "BR1") (pin "1") (pinfunction "+_1") (pintype "bidirectional"))
      (node (ref "C1") (pin "+") (pinfunction "+_+") (pintype "passive"))
      (node (ref "C38") (pin "1") (pinfunction "1_1") (pintype "passive"))
      (node (ref "C39") (pin "1") (pinfunction "1_1") (pintype "passive"))
      (node (ref "IC10") (pin "8") (pinfunction "V+_8") (pintype "power_in"))
      (node (ref "IC7") (pin "3") (pinfunction "VIN_3") (pintype "input"))
      (node (ref "IC9") (pin "8") (pinfunction "V+_8") (pintype "power_in"))
      (node (ref "R11") (pin "1") (pinfunction "1_1") (pintype "passive"))
    )
    (net (code "110") (name "VEE") (class "Default")
      (node (ref "BR1") (pin "2") (pinfunction "-_2") (pintype "bidirectional"))
      (node (ref "C13") (pin "-") (pinfunction "-_-") (pintype "passive"))
      (node (ref "C45") (pin "2") (pinfunction "2_2") (pintype "passive"))
      (node (ref "C46") (pin "2") (pinfunction "2_2") (pintype "passive"))
      (node (ref "IC10") (pin "4") (pinfunction "V-_4") (pintype "power_in"))
      (node (ref "IC9") (pin "4") (pinfunction "V-_4") (pintype "power_in"))
      (node (ref "R30") (pin "1") (pinfunction "1_1") (pintype "passive"))
    )
    (net (code "111") (name "V_OCT") (class "Default")
      (node (ref "C20") (pin "2") (pinfunction "2_2") (pintype "passive"))
      (node (ref "IC4") (pin "1") (pinfunction "OUT_1") (pintype "output"))
      (node (ref "IC5") (pin "20") (pinfunction "PA4/SPI1_NSS/SPI3_NSS/USART2_CK/I2S3_WS/ADC4/DAC1_20") (pintype "bidirectional"))
      (node (ref "R34") (pin "1") (pinfunction "1_1") (pintype "passive"))
    )
    (net (code "112") (name "unconnected-(IC5-PA8{slash}USART1_CK{slash}TIM1_CH1{slash}MCO-Pad41)") (class "Default")
      (node (ref "IC5") (pin "41") (pinfunction "PA8/USART1_CK/TIM1_CH1/MCO_41") (pintype "bidirectional"))
    )
    (net (code "113") (name "unconnected-(IC5-PA11{slash}USART1_CTS{slash}CANRX{slash}USBDM{slash}TIM1_CH4-Pad44)") (class "Default")
      (node (ref "IC5") (pin "44") (pinfunction "PA11/USART1_CTS/CANRX/USBDM/TIM1_CH4_44") (pintype "bidirectional"))
    )
    (net (code "114") (name "unconnected-(IC5-PA12{slash}USART1_RTS{slash}CANTX{slash}USBDP{slash}TIM1_ETR-Pad45)") (class "Default")
      (node (ref "IC5") (pin "45") (pinfunction "PA12/USART1_RTS/CANTX/USBDP/TIM1_ETR_45") (pintype "bidirectional"))
    )
    (net (code "115") (name "unconnected-(IC5-PB4{slash}NJTRST{slash}SPI3_MISO{slash}SPI1_MISO-Pad56)") (class "Default")
      (node (ref "IC5") (pin "56") (pinfunction "PB4/NJTRST/SPI3_MISO/SPI1_MISO_56") (pintype "bidirectional"))
    )
    (net (code "116") (name "unconnected-(IC5-PC6{slash}I2S2_MCK-Pad37)") (class "Default")
      (node (ref "IC5") (pin "37") (pinfunction "PC6/I2S2_MCK_37") (pintype "bidirectional"))
    )
    (net (code "117") (name "unconnected-(IC5-PC7{slash}I2S3_MCK-Pad38)") (class "Default")
      (node (ref "IC5") (pin "38") (pinfunction "PC7/I2S3_MCK_38") (pintype "bidirectional"))
    )
    (net (code "118") (name "unconnected-(IC5-PC8-Pad39)") (class "Default")
      (node (ref "IC5") (pin "39") (pinfunction "PC8_39") (pintype "bidirectional"))
    )
    (net (code "119") (name "unconnected-(IC5-PC9{slash}I2S2_CKIN{slash}I2S3_CKIN-Pad40)") (class "Default")
      (node (ref "IC5") (pin "40") (pinfunction "PC9/I2S2_CKIN/I2S3_CKIN_40") (pintype "bidirectional"))
    )
    (net (code "120") (name "unconnected-(IC5-PC12{slash}UART5_TX{slash}I2S3_SD{slash}USART3_CK-Pad53)") (class "Default")
      (node (ref "IC5") (pin "53") (pinfunction "PC12/UART5_TX/I2S3_SD/USART3_CK_53") (pintype "bidirectional"))
    )
    (net (code "121") (name "unconnected-(IC5-PC13-TAMPER-RTC-Pad2)") (class "Default")
      (node (ref "IC5") (pin "2") (pinfunction "PC13-TAMPER-RTC_2") (pintype "bidirectional"))
    )
    (net (code "122") (name "unconnected-(IC5-PC14{slash}OSC32_IN-Pad3)") (class "Default")
      (node (ref "IC5") (pin "3") (pinfunction "PC14/OSC32_IN_3") (pintype "bidirectional"))
    )
    (net (code "123") (name "unconnected-(IC5-PC15{slash}OSC_OUT-Pad4)") (class "Default")
      (node (ref "IC5") (pin "4") (pinfunction "PC15/OSC_OUT_4") (pintype "bidirectional"))
    )
    (net (code "124") (name "unconnected-(IC5-PD2{slash}TIM3-ETR-Pad54)") (class "Default")
      (node (ref "IC5") (pin "54") (pinfunction "PD2/TIM3-ETR_54") (pintype "bidirectional"))
    )
    (net (code "125") (name "unconnected-(IC8-CLKOUT-Pad2)") (class "Default")
      (node (ref "IC8") (pin "2") (pinfunction "CLKOUT_2") (pintype "bidirectional"))
    )
    (net (code "126") (name "unconnected-(IC8-LHPOUT-Pad9)") (class "Default")
      (node (ref "IC8") (pin "9") (pinfunction "LHPOUT_9") (pintype "bidirectional"))
    )
    (net (code "127") (name "unconnected-(IC8-MICBIAS-Pad17)") (class "Default")
      (node (ref "IC8") (pin "17") (pinfunction "MICBIAS_17") (pintype "bidirectional"))
    )
    (net (code "128") (name "unconnected-(IC8-MICIN-Pad18)") (class "Default")
      (node (ref "IC8") (pin "18") (pinfunction "MICIN_18") (pintype "bidirectional"))
    )
    (net (code "129") (name "unconnected-(IC8-RHPOUT-Pad10)") (class "Default")
      (node (ref "IC8") (pin "10") (pinfunction "RHPOUT_10") (pintype "bidirectional"))
    )
    (net (code "130") (name "unconnected-(IC11-QH*-Pad9)") (class "Default")
      (node (ref "IC11") (pin "9") (pinfunction "QH*_9") (pintype "tri_state"))
    )
    (net (code "131") (name "unconnected-(JP2-Pad7)") (class "Default")
      (node (ref "JP2") (pin "7") (pinfunction "7_7") (pintype "passive"))
    )
  )
)
